# transponder-6_1_1.net
KiCad netlist of a schematic drawn in EAGLE
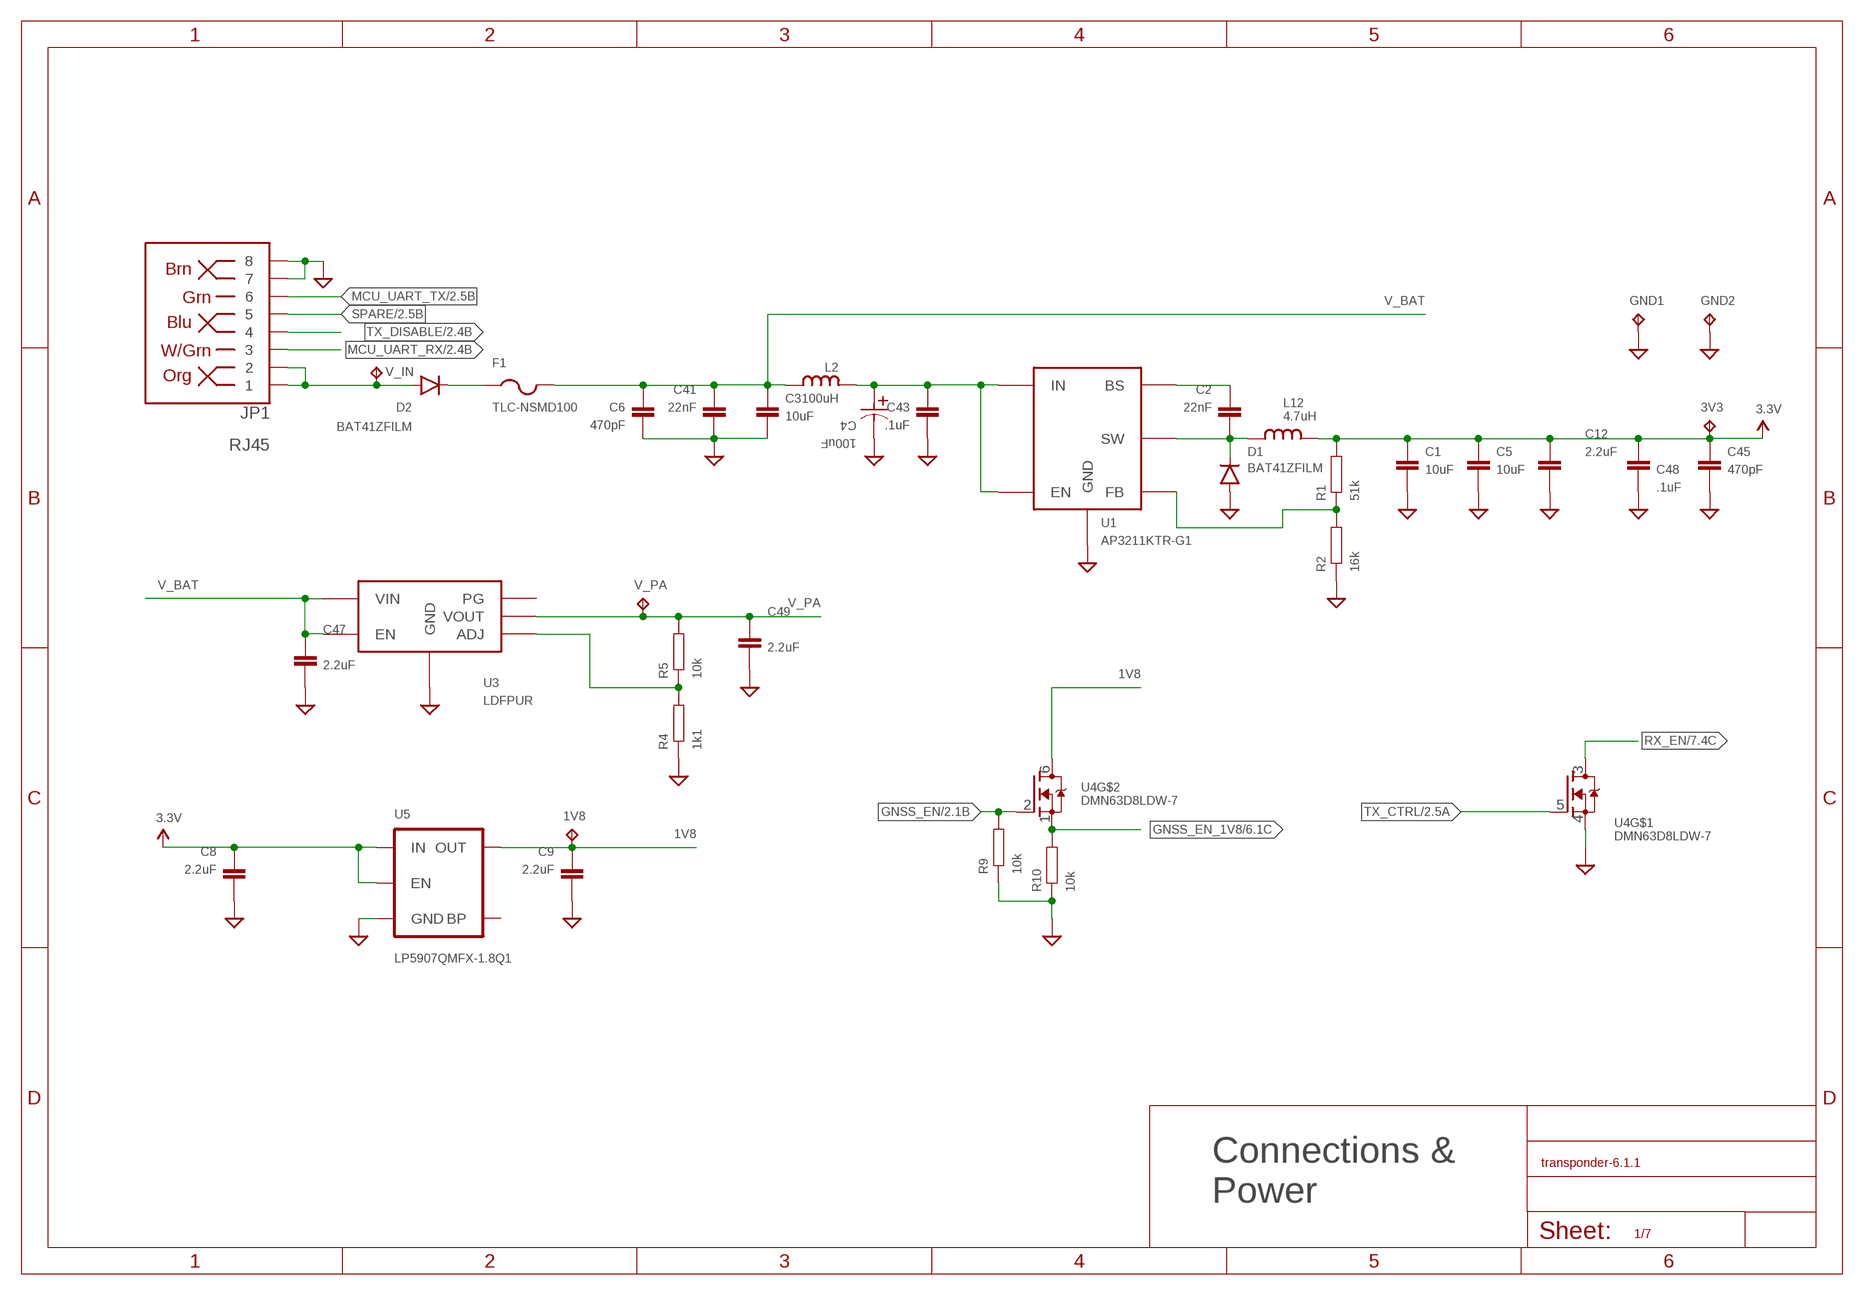
[diagram p0: schematic, sheet 1]
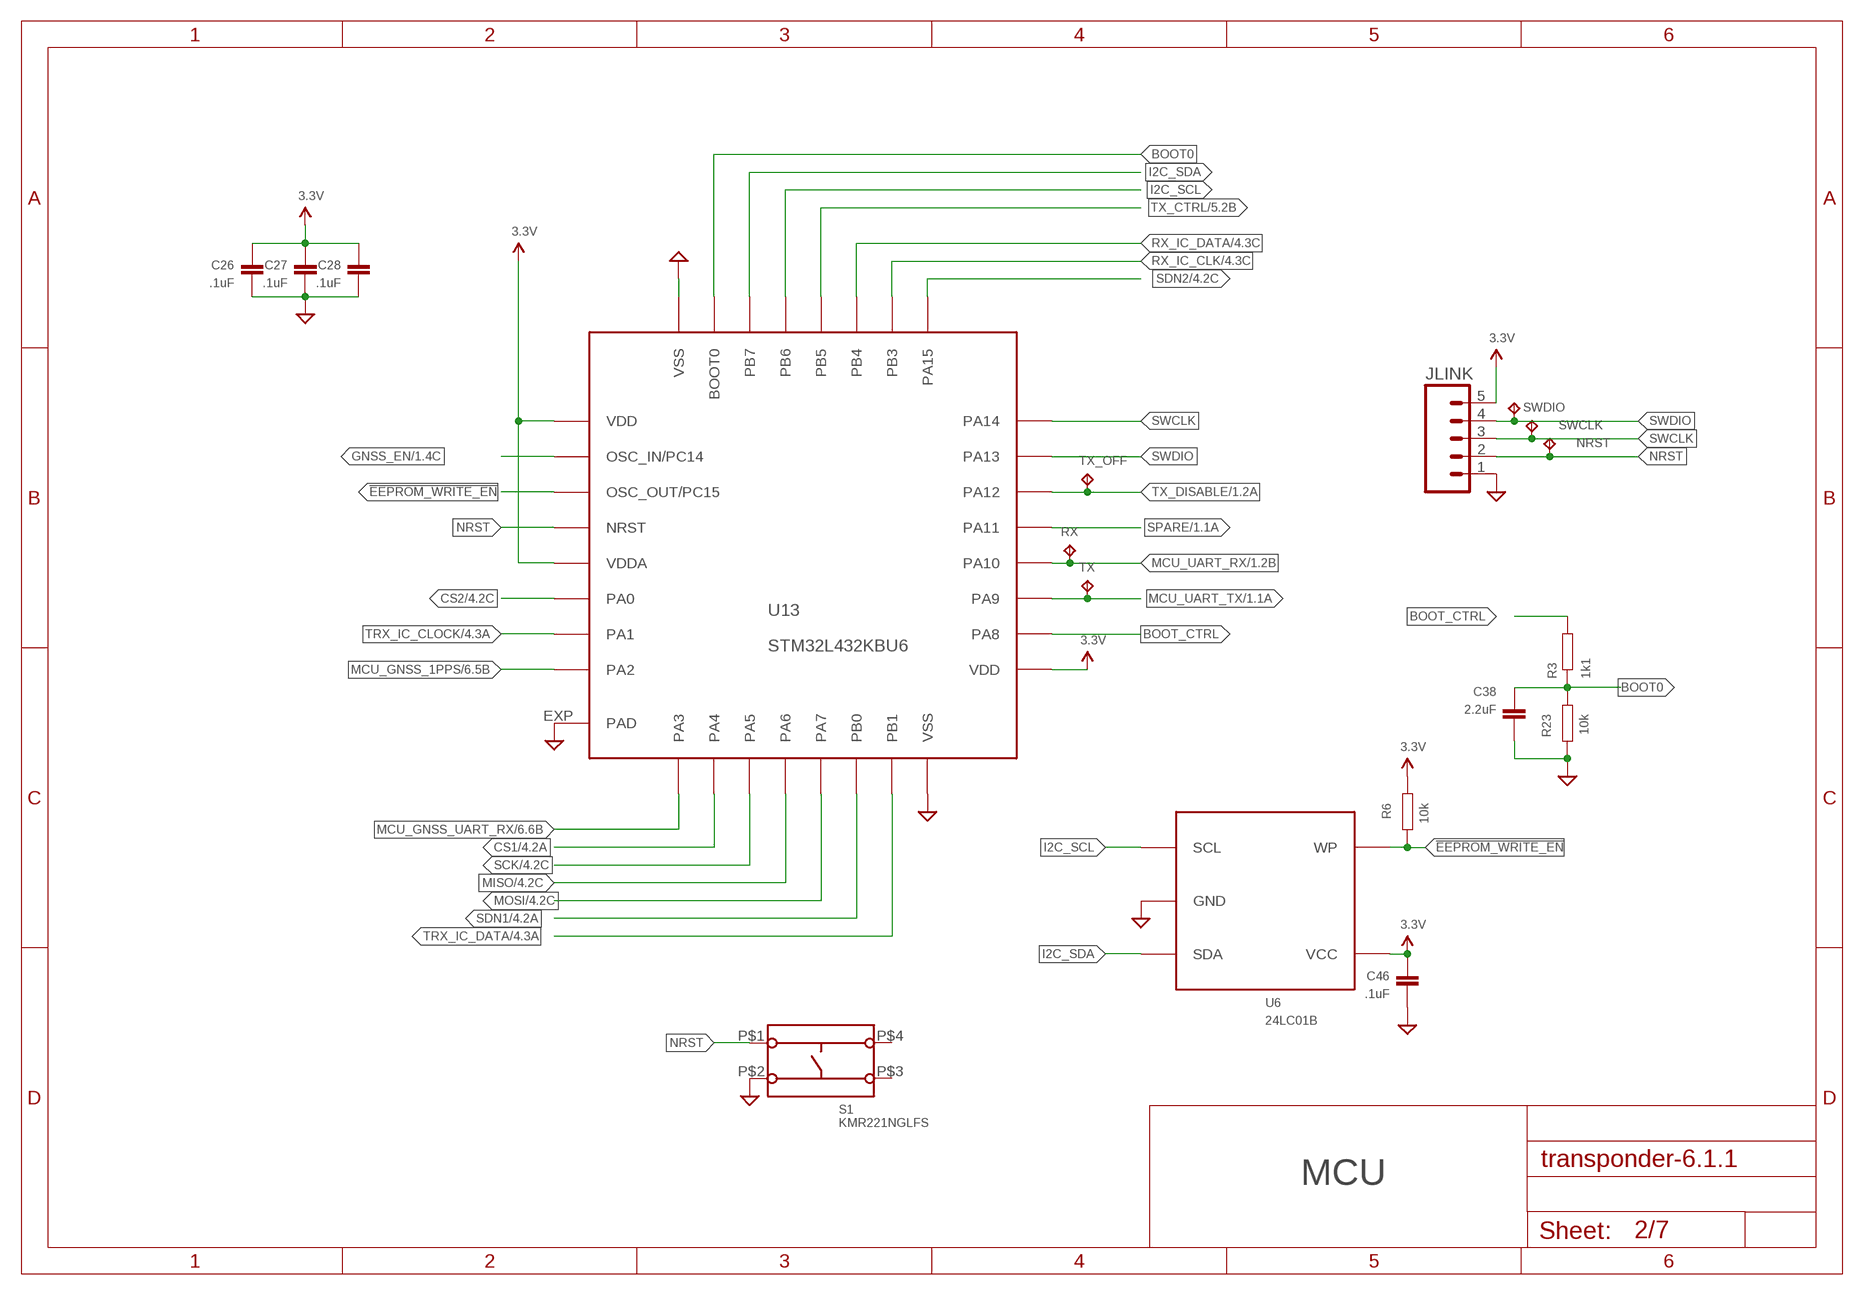
[diagram p1: schematic, sheet 2]
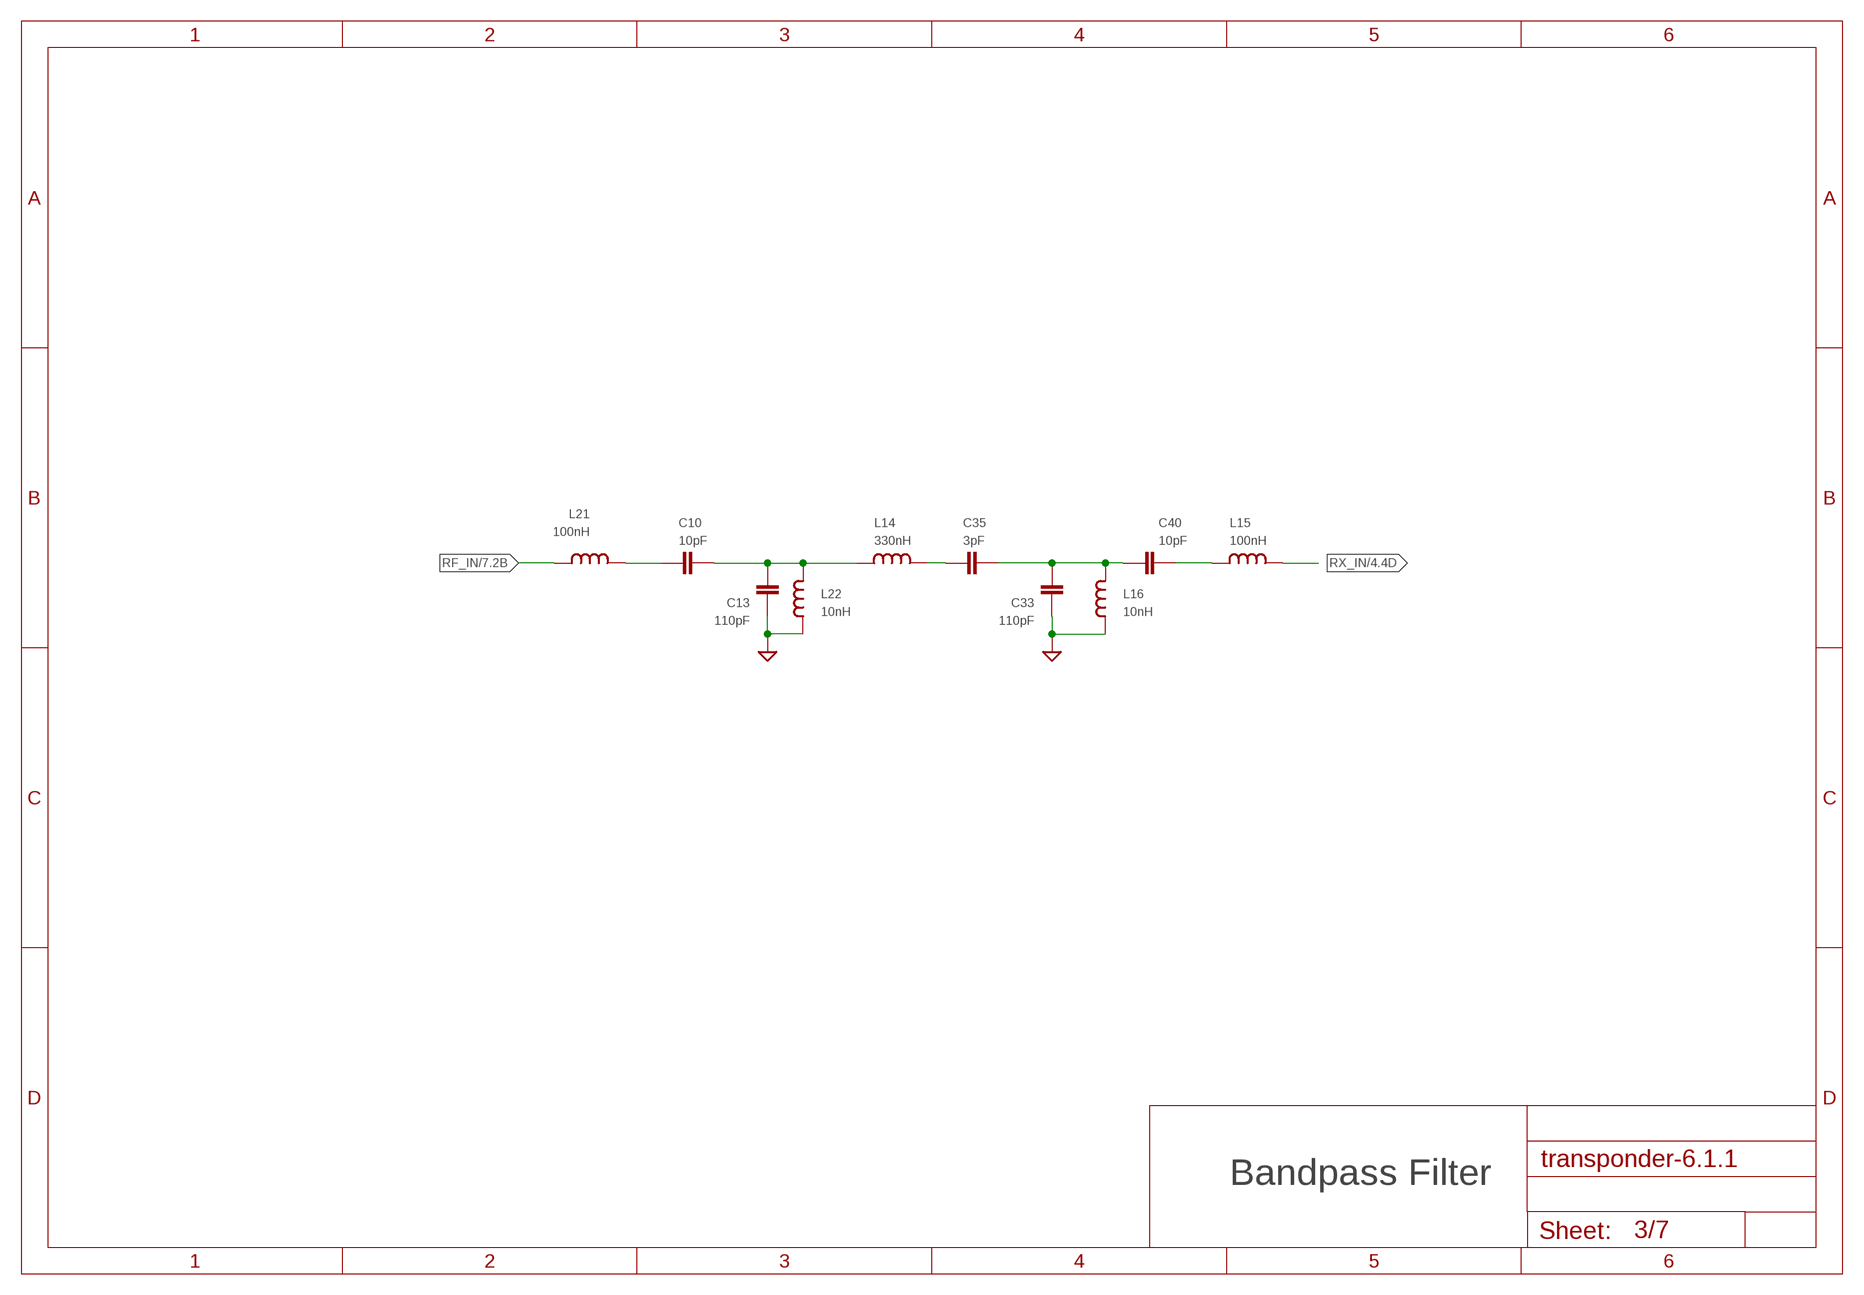
[diagram p2: schematic, sheet 3]
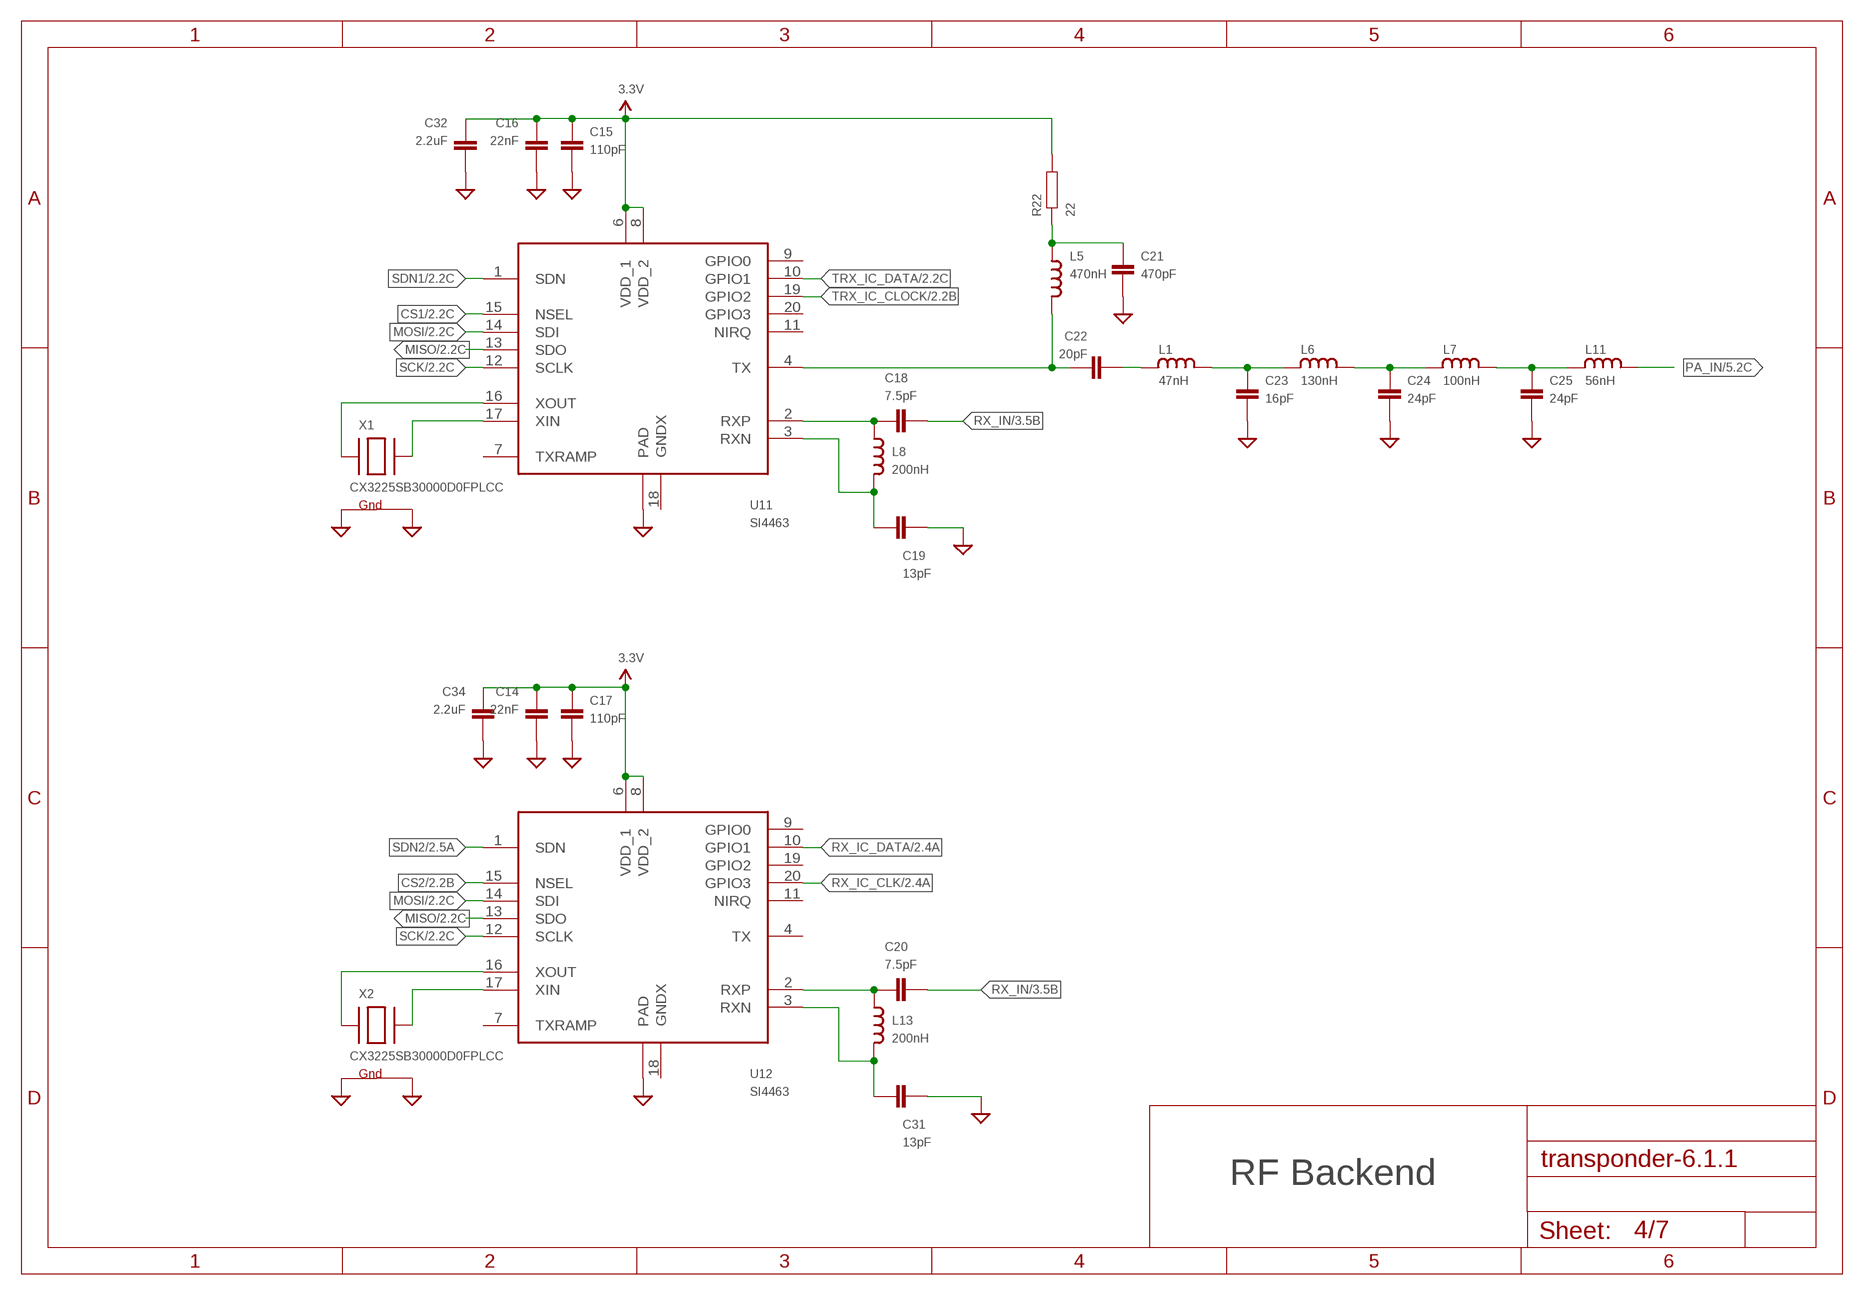
[diagram p3: schematic, sheet 4]
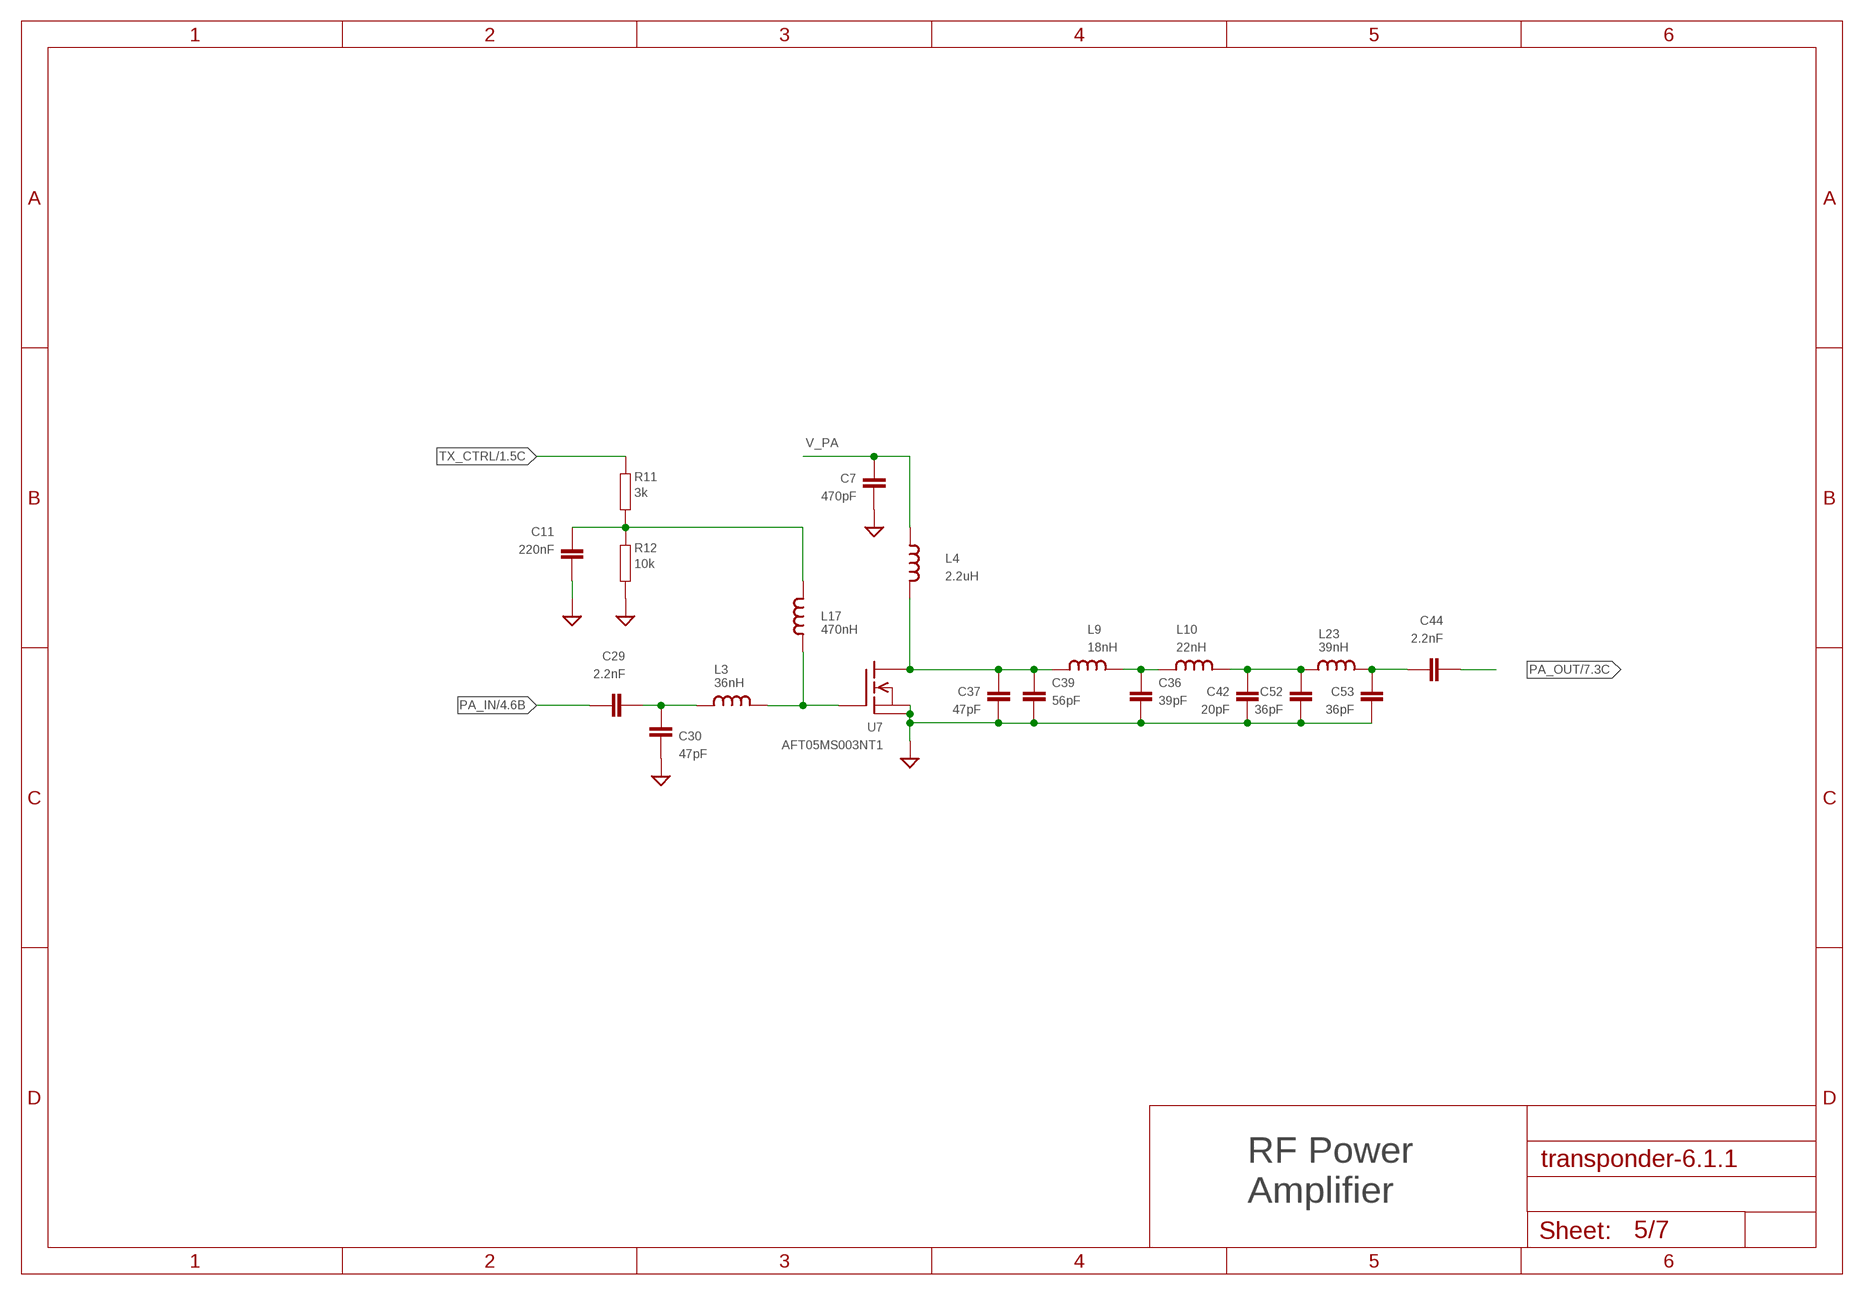
[diagram p4: schematic, sheet 5]
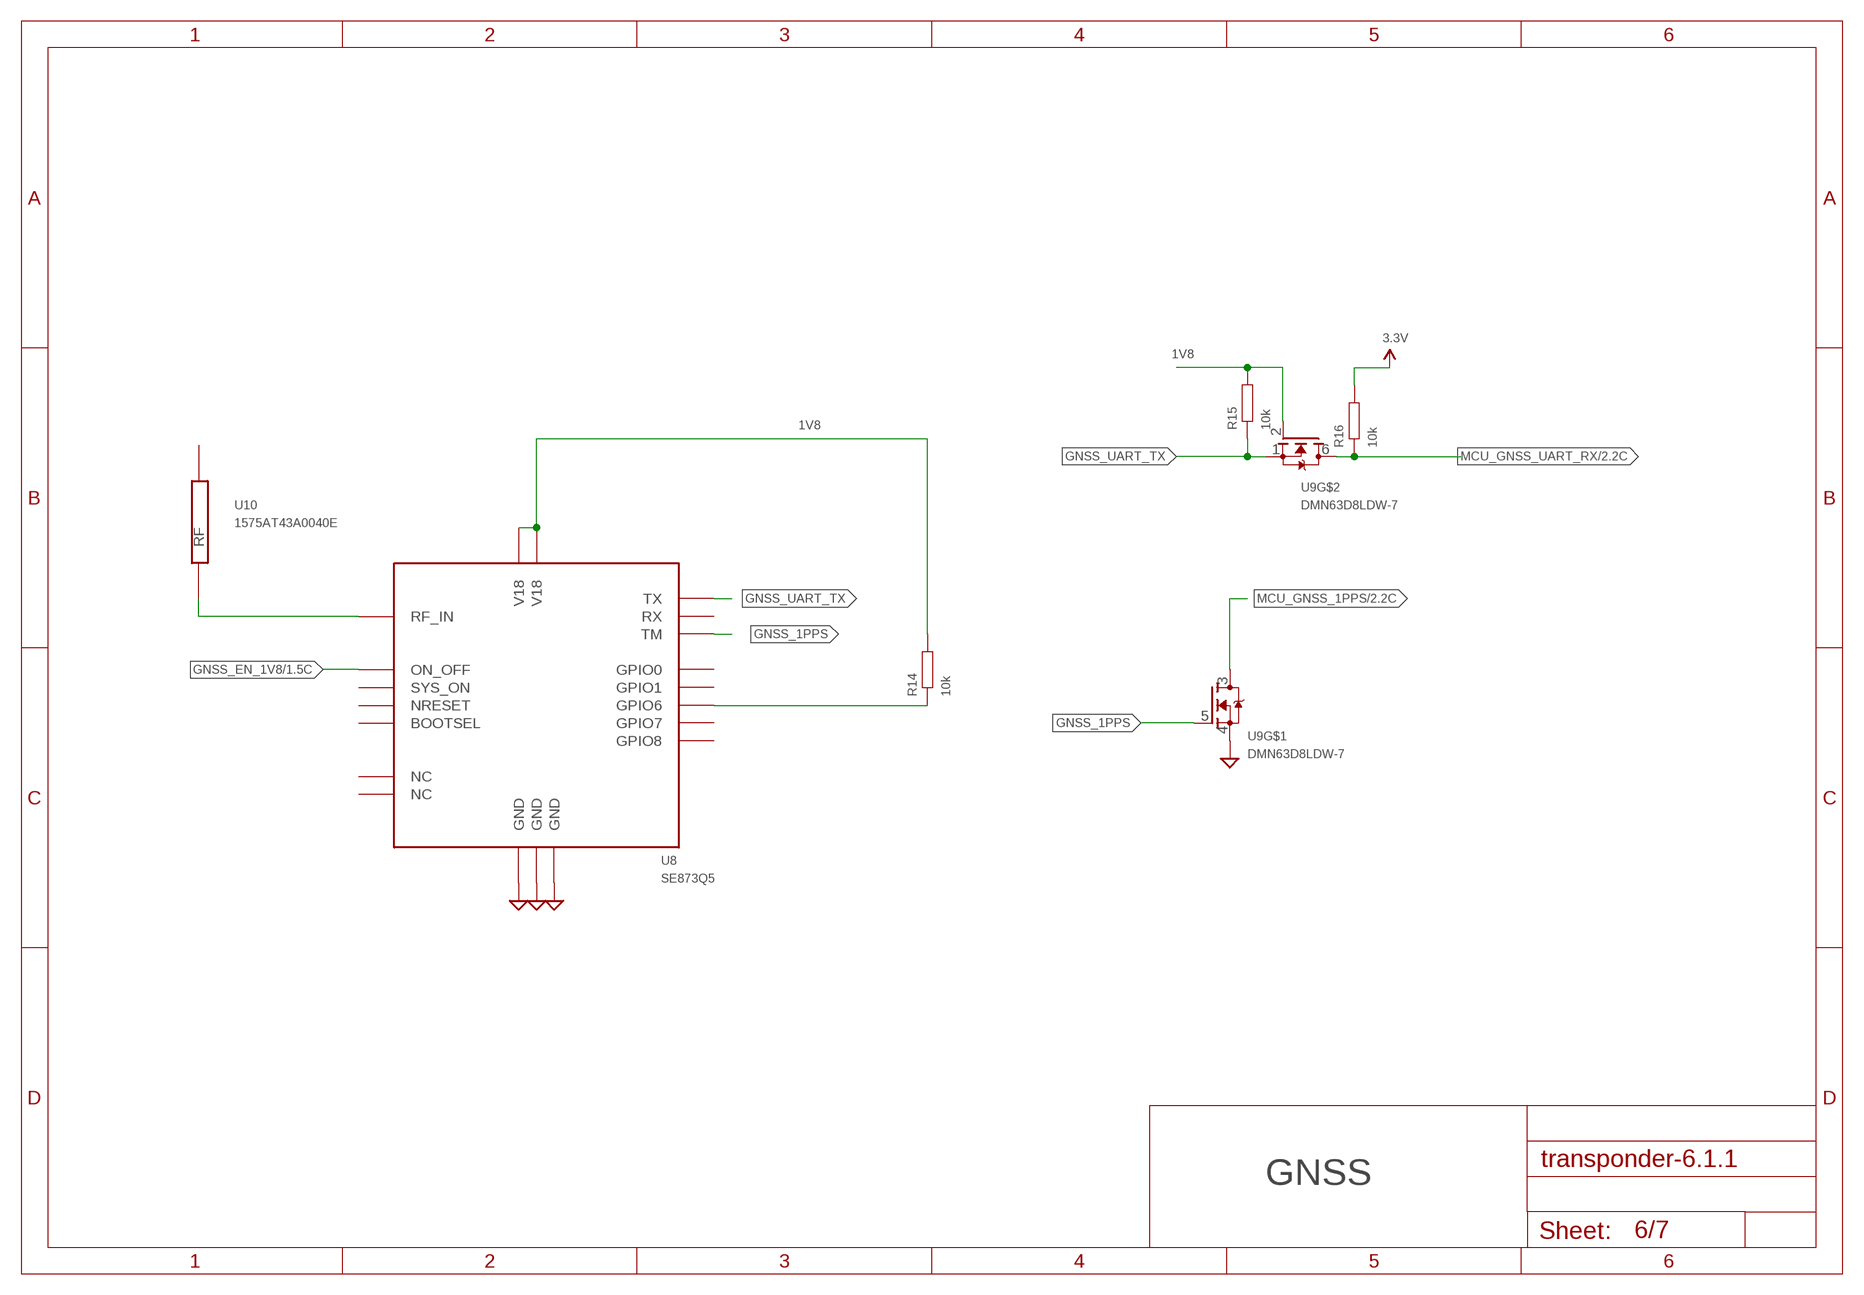
[diagram p5: schematic, sheet 6]
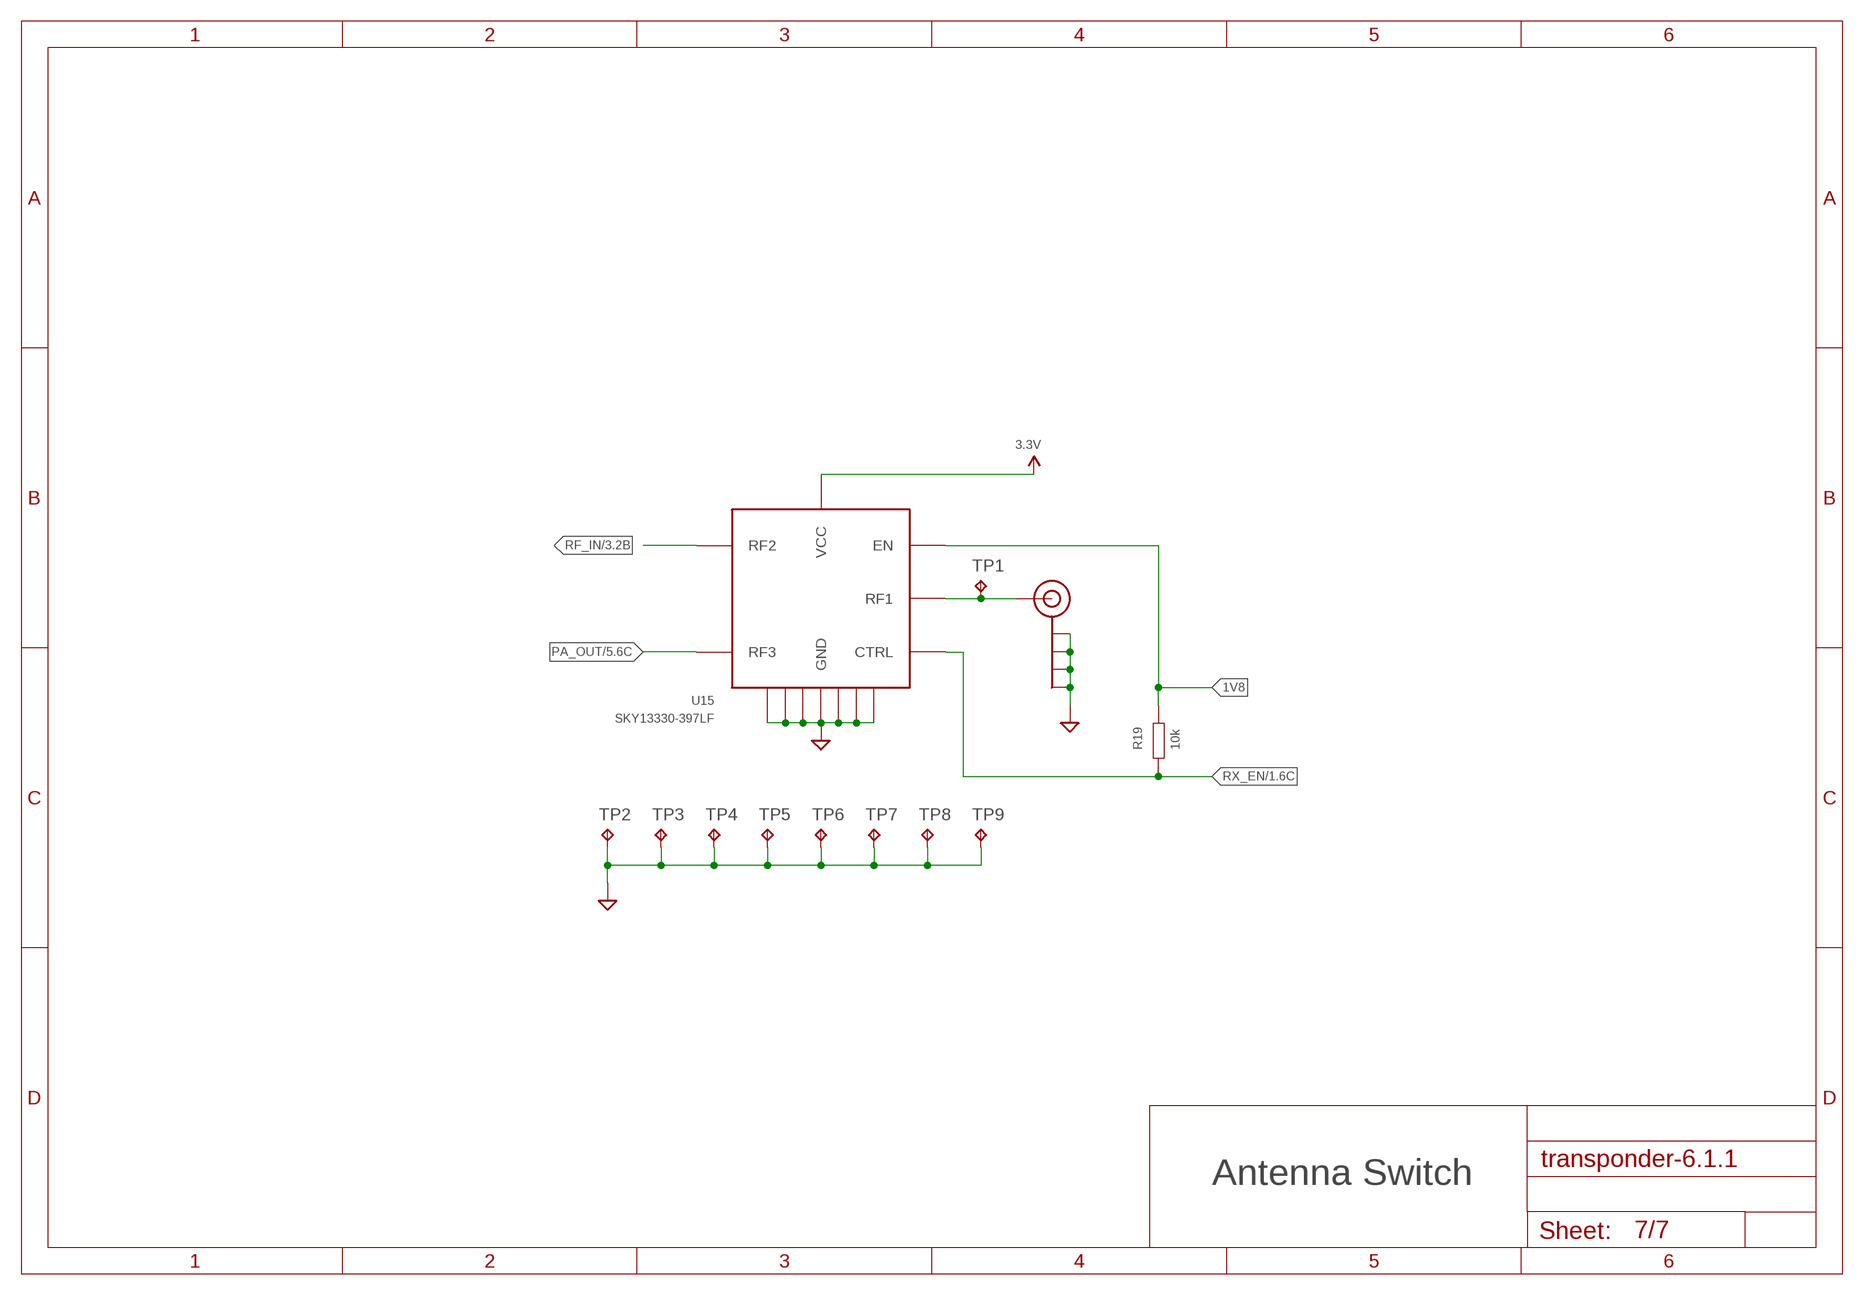
[diagram p6: schematic, sheet 7]

(export (version "E")
  (design (tool "Eeschema 10.0.6"))
  (components
    (comp (ref "C10")
      (value "10pF")
      (footprint "eagle-import:0603")
      (fields (field (name "PARTNO") "06035A100FAT2A"))
      (libsource (lib "eagle-import") (part "CAPACITOR0603"))
    )
    (comp (ref "C13")
      (value "110pF")
      (footprint "eagle-import:0603")
      (fields (field (name "PARTNO") "06035U111FAT2A"))
      (libsource (lib "eagle-import") (part "CAPACITOR0603"))
    )
    (comp (ref "C33")
      (value "110pF")
      (footprint "eagle-import:0603")
      (fields (field (name "PARTNO") "06035U111FAT2A"))
      (libsource (lib "eagle-import") (part "CAPACITOR0603"))
    )
    (comp (ref "C35")
      (value "3pF")
      (footprint "eagle-import:0603")
      (fields (field (name "PARTNO") "06032U3R0BAT2A"))
      (libsource (lib "eagle-import") (part "CAPACITOR0603"))
    )
    (comp (ref "C40")
      (value "10pF")
      (footprint "eagle-import:0603")
      (fields (field (name "PARTNO") "06035A100FAT2A"))
      (libsource (lib "eagle-import") (part "CAPACITOR0603"))
    )
    (comp (ref "L14")
      (value "330nH")
      (footprint "eagle-import:0603")
      (fields (field (name "PARTNO") "LQW18ANR33G00D"))
      (libsource (lib "eagle-import") (part "INDUCTOR0603"))
    )
    (comp (ref "L15")
      (value "100nH")
      (footprint "eagle-import:0603")
      (fields (field (name "PARTNO") "LQW18ANR10G00D"))
      (libsource (lib "eagle-import") (part "INDUCTOR0603"))
    )
    (comp (ref "L16")
      (value "10nH")
      (footprint "eagle-import:0603")
      (fields (field (name "PARTNO") "LQW18AN10NG00D"))
      (libsource (lib "eagle-import") (part "INDUCTOR0603"))
    )
    (comp (ref "L21")
      (value "100nH")
      (footprint "eagle-import:0603")
      (fields (field (name "PARTNO") "LQW18ANR10G00D"))
      (libsource (lib "eagle-import") (part "INDUCTOR0603"))
    )
    (comp (ref "L22")
      (value "10nH")
      (footprint "eagle-import:0603")
      (fields (field (name "PARTNO") "LQW18AN10NG00D"))
      (libsource (lib "eagle-import") (part "INDUCTOR0603"))
    )
    (comp (ref "R14")
      (value "10k")
      (footprint "eagle-import:0603-RES")
      (fields (field (name "PARTNO") "RC0603JR-0710KL"))
      (libsource (lib "eagle-import") (part "RESISTOR0603-RES"))
    )
    (comp (ref "R15")
      (value "10k")
      (footprint "eagle-import:0603-RES")
      (fields (field (name "PARTNO") "RC0603JR-0710KL"))
      (libsource (lib "eagle-import") (part "RESISTOR0603-RES"))
    )
    (comp (ref "R16")
      (value "10k")
      (footprint "eagle-import:0603-RES")
      (fields (field (name "PARTNO") "RC0603JR-0710KL"))
      (libsource (lib "eagle-import") (part "RESISTOR0603-RES"))
    )
    (comp (ref "U8")
      (value "SE873Q5")
      (footprint "eagle-import:SE873")
      (libsource (lib "eagle-import") (part "SE873"))
    )
    (comp (ref "U9")
      (value "DMN63D8LDW-7")
      (footprint "eagle-import:SOT363")
      (fields (field (name "PARTNO") "DMN63D8LDW-7"))
      (libsource (lib "eagle-import") (part "DMN63D8LDW"))
    )
    (comp (ref "U10")
      (value "1575AT43A0040E")
      (footprint "eagle-import:1575AT43A0040E")
      (libsource (lib "eagle-import") (part "1575AT43A0040E"))
    )
    (comp (ref "1V8")
      (value "TPTP16R")
      (footprint "eagle-import:TP16R")
      (libsource (lib "eagle-import") (part "TPTP16R"))
    )
    (comp (ref "3V3")
      (value "TPTP16R")
      (footprint "eagle-import:TP16R")
      (libsource (lib "eagle-import") (part "TPTP16R"))
    )
    (comp (ref "C1")
      (value "10uF")
      (footprint "eagle-import:0805")
      (fields (field (name "PARTNO") " EMK212ABJ106KG-T"))
      (libsource (lib "eagle-import") (part "CAPACITOR0805"))
    )
    (comp (ref "C2")
      (value "22nF")
      (footprint "eagle-import:0603")
      (fields (field (name "PARTNO") "GRM188R71E223KA01D"))
      (libsource (lib "eagle-import") (part "CAPACITOR0603"))
    )
    (comp (ref "C3")
      (value "10uF")
      (footprint "eagle-import:0805")
      (fields (field (name "PARTNO") " EMK212ABJ106KG-T"))
      (libsource (lib "eagle-import") (part "CAPACITOR0805"))
    )
    (comp (ref "C4")
      (value "100uF")
      (footprint "eagle-import:PCAP_6.3X5.4-ELECT")
      (fields (field (name "MF") "Nichicon") (field (name "MP") "UWX1C101MCL1GB"))
      (libsource (lib "eagle-import") (part "UWX1C101MCL1GB"))
    )
    (comp (ref "C5")
      (value "10uF")
      (footprint "eagle-import:0805")
      (fields (field (name "PARTNO") " EMK212ABJ106KG-T"))
      (libsource (lib "eagle-import") (part "CAPACITOR0805"))
    )
    (comp (ref "C6")
      (value "470pF")
      (footprint "eagle-import:0603")
      (fields (field (name "PARTNO") "GCM1885C2A471JA16J"))
      (libsource (lib "eagle-import") (part "CAPACITOR0603"))
    )
    (comp (ref "C8")
      (value "2.2uF")
      (footprint "eagle-import:0603")
      (fields (field (name "PARTNO") "EMK107BJ225KA-T"))
      (libsource (lib "eagle-import") (part "CAPACITOR0603"))
    )
    (comp (ref "C9")
      (value "2.2uF")
      (footprint "eagle-import:0603")
      (fields (field (name "PARTNO") "EMK107BJ225KA-T"))
      (libsource (lib "eagle-import") (part "CAPACITOR0603"))
    )
    (comp (ref "C12")
      (value "2.2uF")
      (footprint "eagle-import:0603")
      (fields (field (name "PARTNO") "EMK107BJ225KA-T"))
      (libsource (lib "eagle-import") (part "CAPACITOR0603"))
    )
    (comp (ref "C41")
      (value "22nF")
      (footprint "eagle-import:0603")
      (fields (field (name "PARTNO") "GRM188R71E223KA01D"))
      (libsource (lib "eagle-import") (part "CAPACITOR0603"))
    )
    (comp (ref "C43")
      (value ".1uF")
      (footprint "eagle-import:0603")
      (fields (field (name "PARTNO") "EMK107B7104KAHT"))
      (libsource (lib "eagle-import") (part "CAPACITOR0603"))
    )
    (comp (ref "C45")
      (value "470pF")
      (footprint "eagle-import:0603")
      (fields (field (name "PARTNO") "GCM1885C2A471JA16J"))
      (libsource (lib "eagle-import") (part "CAPACITOR0603"))
    )
    (comp (ref "C47")
      (value "2.2uF")
      (footprint "eagle-import:0603")
      (fields (field (name "PARTNO") "EMK107BJ225KA-T"))
      (libsource (lib "eagle-import") (part "CAPACITOR0603"))
    )
    (comp (ref "C48")
      (value ".1uF")
      (footprint "eagle-import:0603")
      (fields (field (name "PARTNO") "EMK107B7104KAHT"))
      (libsource (lib "eagle-import") (part "CAPACITOR0603"))
    )
    (comp (ref "C49")
      (value "2.2uF")
      (footprint "eagle-import:0603")
      (fields (field (name "PARTNO") "EMK107BJ225KA-T"))
      (libsource (lib "eagle-import") (part "CAPACITOR0603"))
    )
    (comp (ref "D1")
      (value "BAT41ZFILM")
      (footprint "eagle-import:SOD-123")
      (libsource (lib "eagle-import") (part "DIODESOD123"))
    )
    (comp (ref "D2")
      (value "BAT41ZFILM")
      (footprint "eagle-import:SOD-123")
      (libsource (lib "eagle-import") (part "DIODESOD123"))
    )
    (comp (ref "F1")
      (value "TLC-NSMD100")
      (footprint "eagle-import:R1206")
      (libsource (lib "eagle-import") (part "PTCFUSE-1206"))
    )
    (comp (ref "GND1")
      (value "TPTP16R")
      (footprint "eagle-import:TP16R")
      (libsource (lib "eagle-import") (part "TPTP16R"))
    )
    (comp (ref "GND2")
      (value "TPTP16R")
      (footprint "eagle-import:TP16R")
      (libsource (lib "eagle-import") (part "TPTP16R"))
    )
    (comp (ref "JP1")
      (value "RJ45")
      (footprint "eagle-import:RJ45-8")
      (fields (field (name "PARTNO") "54602-908LF"))
      (libsource (lib "eagle-import") (part "RJ45-8PTH"))
    )
    (comp (ref "L2")
      (value "100uH")
      (footprint "eagle-import:1206")
      (fields (field (name "PARTNO") "CBC3225T101KRV"))
      (libsource (lib "eagle-import") (part "INDUCTOR1206"))
    )
    (comp (ref "L12")
      (value "4.7uH")
      (footprint "eagle-import:0805")
      (fields (field (name "PARTNO") "MLZ2012M4R7WT000"))
      (libsource (lib "eagle-import") (part "INDUCTOR0805"))
    )
    (comp (ref "R1")
      (value "51k")
      (footprint "eagle-import:0603-RES")
      (fields (field (name "PARTNO") "RC0603JR-0751KL"))
      (libsource (lib "eagle-import") (part "RESISTOR0603-RES"))
    )
    (comp (ref "R2")
      (value "16k")
      (footprint "eagle-import:0603-RES")
      (fields (field (name "PARTNO") "RC0603FR-1016KL"))
      (libsource (lib "eagle-import") (part "RESISTOR0603-RES"))
    )
    (comp (ref "R4")
      (value "1k1")
      (footprint "eagle-import:0603-RES")
      (fields (field (name "PARTNO") "RC0603JR-071K1L"))
      (libsource (lib "eagle-import") (part "RESISTOR0603-RES"))
    )
    (comp (ref "R5")
      (value "10k")
      (footprint "eagle-import:0603-RES")
      (fields (field (name "PARTNO") "RC0603JR-0710KL"))
      (libsource (lib "eagle-import") (part "RESISTOR0603-RES"))
    )
    (comp (ref "R9")
      (value "10k")
      (footprint "eagle-import:0603-RES")
      (fields (field (name "PARTNO") "RC0603JR-0710KL"))
      (libsource (lib "eagle-import") (part "RESISTOR0603-RES"))
    )
    (comp (ref "R10")
      (value "10k")
      (footprint "eagle-import:0603-RES")
      (fields (field (name "PARTNO") "RC0603JR-0710KL"))
      (libsource (lib "eagle-import") (part "RESISTOR0603-RES"))
    )
    (comp (ref "U1")
      (value "AP3211KTR-G1")
      (footprint "eagle-import:SOT23-6")
      (libsource (lib "eagle-import") (part "AP3211"))
    )
    (comp (ref "U3")
      (value "LDFPUR")
      (footprint "eagle-import:DFN-6")
      (libsource (lib "eagle-import") (part "LDF"))
    )
    (comp (ref "U4")
      (value "DMN63D8LDW-7")
      (footprint "eagle-import:SOT363")
      (fields (field (name "PARTNO") "DMN63D8LDW-7"))
      (libsource (lib "eagle-import") (part "DMN63D8LDW"))
    )
    (comp (ref "U5")
      (value "LP5907QMFX-1.8Q1")
      (footprint "eagle-import:SOT23-5")
      (fields (field (name "PARTNO") "LP5907QMFX-1.8Q1 "))
      (libsource (lib "eagle-import") (part "V_REG_LDOSMD"))
    )
    (comp (ref "V_IN")
      (value "TPTP16R")
      (footprint "eagle-import:TP16R")
      (libsource (lib "eagle-import") (part "TPTP16R"))
    )
    (comp (ref "V_PA")
      (value "TPTP16R")
      (footprint "eagle-import:TP16R")
      (libsource (lib "eagle-import") (part "TPTP16R"))
    )
    (comp (ref "J$1")
      (value "SMA_EDGE")
      (footprint "eagle-import:SMA-EDGE")
      (libsource (lib "eagle-import") (part "SMA_EDGE"))
    )
    (comp (ref "R19")
      (value "10k")
      (footprint "eagle-import:0603-RES")
      (fields (field (name "PARTNO") "RC0603JR-0710KL"))
      (libsource (lib "eagle-import") (part "RESISTOR0603-RES"))
    )
    (comp (ref "TP1")
      (value "TPTP10R")
      (footprint "eagle-import:TP10R")
      (libsource (lib "eagle-import") (part "TPTP10R"))
    )
    (comp (ref "TP2")
      (value "TPTP10R")
      (footprint "eagle-import:TP10R")
      (libsource (lib "eagle-import") (part "TPTP10R"))
    )
    (comp (ref "TP3")
      (value "TPTP10R")
      (footprint "eagle-import:TP10R")
      (libsource (lib "eagle-import") (part "TPTP10R"))
    )
    (comp (ref "TP4")
      (value "TPTP10R")
      (footprint "eagle-import:TP10R")
      (libsource (lib "eagle-import") (part "TPTP10R"))
    )
    (comp (ref "TP5")
      (value "TPTP10R")
      (footprint "eagle-import:TP10R")
      (libsource (lib "eagle-import") (part "TPTP10R"))
    )
    (comp (ref "TP6")
      (value "TPTP10R")
      (footprint "eagle-import:TP10R")
      (libsource (lib "eagle-import") (part "TPTP10R"))
    )
    (comp (ref "TP7")
      (value "TPTP10R")
      (footprint "eagle-import:TP10R")
      (libsource (lib "eagle-import") (part "TPTP10R"))
    )
    (comp (ref "TP8")
      (value "TPTP10R")
      (footprint "eagle-import:TP10R")
      (libsource (lib "eagle-import") (part "TPTP10R"))
    )
    (comp (ref "TP9")
      (value "TPTP10R")
      (footprint "eagle-import:TP10R")
      (libsource (lib "eagle-import") (part "TPTP10R"))
    )
    (comp (ref "U15")
      (value "SKY13330-397LF")
      (footprint "eagle-import:QFN12")
      (libsource (lib "eagle-import") (part "SKYWORKS-13330397LF"))
    )
    (comp (ref "C26")
      (value ".1uF")
      (footprint "eagle-import:0603")
      (fields (field (name "PARTNO") "EMK107B7104KAHT"))
      (libsource (lib "eagle-import") (part "CAPACITOR0603"))
    )
    (comp (ref "C27")
      (value ".1uF")
      (footprint "eagle-import:0603")
      (fields (field (name "PARTNO") "EMK107B7104KAHT"))
      (libsource (lib "eagle-import") (part "CAPACITOR0603"))
    )
    (comp (ref "C28")
      (value ".1uF")
      (footprint "eagle-import:0603")
      (fields (field (name "PARTNO") "EMK107B7104KAHT"))
      (libsource (lib "eagle-import") (part "CAPACITOR0603"))
    )
    (comp (ref "C38")
      (value "2.2uF")
      (footprint "eagle-import:0603")
      (fields (field (name "PARTNO") "EMK107BJ225KA-T"))
      (libsource (lib "eagle-import") (part "CAPACITOR0603"))
    )
    (comp (ref "C46")
      (value ".1uF")
      (footprint "eagle-import:0603")
      (fields (field (name "PARTNO") "EMK107B7104KAHT"))
      (libsource (lib "eagle-import") (part "CAPACITOR0603"))
    )
    (comp (ref "JLINK")
      (value "M05PTH")
      (footprint "eagle-import:1X05")
      (libsource (lib "eagle-import") (part "M05PTH"))
    )
    (comp (ref "NRST")
      (value "TPTP16R")
      (footprint "eagle-import:TP16R")
      (libsource (lib "eagle-import") (part "TPTP16R"))
    )
    (comp (ref "R3")
      (value "1k1")
      (footprint "eagle-import:0603-RES")
      (fields (field (name "PARTNO") "RC0603JR-071K1L"))
      (libsource (lib "eagle-import") (part "RESISTOR0603-RES"))
    )
    (comp (ref "R6")
      (value "10k")
      (footprint "eagle-import:0603-RES")
      (fields (field (name "PARTNO") "RC0603JR-0710KL"))
      (libsource (lib "eagle-import") (part "RESISTOR0603-RES"))
    )
    (comp (ref "R23")
      (value "10k")
      (footprint "eagle-import:0603-RES")
      (fields (field (name "PARTNO") "RC0603JR-0710KL"))
      (libsource (lib "eagle-import") (part "RESISTOR0603-RES"))
    )
    (comp (ref "RX")
      (value "TPTP12R")
      (footprint "eagle-import:TP12R")
      (libsource (lib "eagle-import") (part "TPTP12R"))
    )
    (comp (ref "S1")
      (value "KMR221NGLFS")
      (footprint "eagle-import:KMR221NGLFS")
      (libsource (lib "eagle-import") (part "KMR221NGLFS"))
    )
    (comp (ref "SWCLK")
      (value "TPTP16R")
      (footprint "eagle-import:TP16R")
      (libsource (lib "eagle-import") (part "TPTP16R"))
    )
    (comp (ref "SWDIO")
      (value "TPTP16R")
      (footprint "eagle-import:TP16R")
      (libsource (lib "eagle-import") (part "TPTP16R"))
    )
    (comp (ref "TX")
      (value "TPTP12R")
      (footprint "eagle-import:TP12R")
      (libsource (lib "eagle-import") (part "TPTP12R"))
    )
    (comp (ref "TX_OFF")
      (value "TPTP16R")
      (footprint "eagle-import:TP16R")
      (libsource (lib "eagle-import") (part "TPTP16R"))
    )
    (comp (ref "U6")
      (value "24LC01B")
      (footprint "eagle-import:SOT23-5")
      (fields (field (name "PARTNO") "24LC01BT-I/OT"))
      (libsource (lib "eagle-import") (part "24LC01B"))
    )
    (comp (ref "U13")
      (value "STM32L432KBU6")
      (footprint "eagle-import:QFN32")
      (libsource (lib "eagle-import") (part "STM32L432KXXX"))
    )
    (comp (ref "C14")
      (value "22nF")
      (footprint "eagle-import:0603")
      (fields (field (name "PARTNO") "GRM188R71E223KA01D"))
      (libsource (lib "eagle-import") (part "CAPACITOR0603"))
    )
    (comp (ref "C15")
      (value "110pF")
      (footprint "eagle-import:0603")
      (fields (field (name "PARTNO") "06035U111FAT2A"))
      (libsource (lib "eagle-import") (part "CAPACITOR0603"))
    )
    (comp (ref "C16")
      (value "22nF")
      (footprint "eagle-import:0603")
      (fields (field (name "PARTNO") "GRM188R71E223KA01D"))
      (libsource (lib "eagle-import") (part "CAPACITOR0603"))
    )
    (comp (ref "C17")
      (value "110pF")
      (footprint "eagle-import:0603")
      (fields (field (name "PARTNO") "06035U111FAT2A"))
      (libsource (lib "eagle-import") (part "CAPACITOR0603"))
    )
    (comp (ref "C18")
      (value "7.5pF")
      (footprint "eagle-import:0603")
      (fields (field (name "PARTNO") "GRM1885C1H7R5DA01D"))
      (libsource (lib "eagle-import") (part "CAPACITOR0603"))
    )
    (comp (ref "C19")
      (value "13pF")
      (footprint "eagle-import:0603")
      (fields (field (name "PARTNO") "GRM1885C1H130JA01D"))
      (libsource (lib "eagle-import") (part "CAPACITOR0603"))
    )
    (comp (ref "C20")
      (value "7.5pF")
      (footprint "eagle-import:0603")
      (fields (field (name "PARTNO") "GRM1885C1H7R5DA01D"))
      (libsource (lib "eagle-import") (part "CAPACITOR0603"))
    )
    (comp (ref "C21")
      (value "470pF")
      (footprint "eagle-import:0603")
      (fields (field (name "PARTNO") "GCM1885C2A471JA16J"))
      (libsource (lib "eagle-import") (part "CAPACITOR0603"))
    )
    (comp (ref "C22")
      (value "20pF")
      (footprint "eagle-import:0603")
      (fields (field (name "PARTNO") "GRM1885C1H200JA01D"))
      (libsource (lib "eagle-import") (part "CAPACITOR0603"))
    )
    (comp (ref "C23")
      (value "16pF")
      (footprint "eagle-import:0603")
      (fields (field (name "PARTNO") "GCM1885C2A160JA16D"))
      (libsource (lib "eagle-import") (part "CAPACITOR0603"))
    )
    (comp (ref "C24")
      (value "24pF")
      (footprint "eagle-import:0603")
      (fields (field (name "PARTNO") "GCM1885C2A240JA16D"))
      (libsource (lib "eagle-import") (part "CAPACITOR0603"))
    )
    (comp (ref "C25")
      (value "24pF")
      (footprint "eagle-import:0603")
      (fields (field (name "PARTNO") "GCM1885C2A240JA16D"))
      (libsource (lib "eagle-import") (part "CAPACITOR0603"))
    )
    (comp (ref "C31")
      (value "13pF")
      (footprint "eagle-import:0603")
      (fields (field (name "PARTNO") "GRM1885C1H130JA01D"))
      (libsource (lib "eagle-import") (part "CAPACITOR0603"))
    )
    (comp (ref "C32")
      (value "2.2uF")
      (footprint "eagle-import:0603")
      (fields (field (name "PARTNO") "EMK107BJ225KA-T"))
      (libsource (lib "eagle-import") (part "CAPACITOR0603"))
    )
    (comp (ref "C34")
      (value "2.2uF")
      (footprint "eagle-import:0603")
      (fields (field (name "PARTNO") "EMK107BJ225KA-T"))
      (libsource (lib "eagle-import") (part "CAPACITOR0603"))
    )
    (comp (ref "L1")
      (value "47nH")
      (footprint "eagle-import:0603")
      (fields (field (name "PARTNO") "LQW18AS47NG00D"))
      (libsource (lib "eagle-import") (part "INDUCTOR0603"))
    )
    (comp (ref "L5")
      (value "470nH")
      (footprint "eagle-import:0603")
      (fields (field (name "PARTNO") "HK1608R47J-T"))
      (libsource (lib "eagle-import") (part "INDUCTOR0603"))
    )
    (comp (ref "L6")
      (value "130nH")
      (footprint "eagle-import:0603")
      (fields (field (name "PARTNO") "LQW18ANR13G00D"))
      (libsource (lib "eagle-import") (part "INDUCTOR0603"))
    )
    (comp (ref "L7")
      (value "100nH")
      (footprint "eagle-import:0603")
      (fields (field (name "PARTNO") "LQW18ANR10G00D"))
      (libsource (lib "eagle-import") (part "INDUCTOR0603"))
    )
    (comp (ref "L8")
      (value "200nH")
      (footprint "eagle-import:0603")
      (fields (field (name "PARTNO") "LQW18ANR20J00D"))
      (libsource (lib "eagle-import") (part "INDUCTOR0603"))
    )
    (comp (ref "L11")
      (value "56nH")
      (footprint "eagle-import:0603")
      (fields (field (name "PARTNO") "LQW18AN56NG00D"))
      (libsource (lib "eagle-import") (part "INDUCTOR0603"))
    )
    (comp (ref "L13")
      (value "200nH")
      (footprint "eagle-import:0603")
      (fields (field (name "PARTNO") "LQW18ANR20J00D"))
      (libsource (lib "eagle-import") (part "INDUCTOR0603"))
    )
    (comp (ref "R22")
      (value "22")
      (footprint "eagle-import:0603-RES")
      (fields (field (name "PARTNO") "RC0603JR-0722RL"))
      (libsource (lib "eagle-import") (part "RESISTOR0603-RES"))
    )
    (comp (ref "U11")
      (value "SI4463")
      (footprint "eagle-import:SI4463")
      (fields (field (name "PARTNO") "SI4463-C2A-GMR"))
      (libsource (lib "eagle-import") (part "SI4463"))
    )
    (comp (ref "U12")
      (value "SI4463")
      (footprint "eagle-import:SI4463")
      (fields (field (name "PARTNO") "SI4463-C2A-GMR"))
      (libsource (lib "eagle-import") (part "SI4463"))
    )
    (comp (ref "X1")
      (value "CX3225SB30000D0FPLCC")
      (footprint "eagle-import:NX3225")
      (libsource (lib "eagle-import") (part "XTAL-4-3225"))
    )
    (comp (ref "X2")
      (value "CX3225SB30000D0FPLCC")
      (footprint "eagle-import:NX3225")
      (libsource (lib "eagle-import") (part "XTAL-4-3225"))
    )
    (comp (ref "C7")
      (value "470pF")
      (footprint "eagle-import:0603")
      (fields (field (name "PARTNO") "GCM1885C2A471JA16J"))
      (libsource (lib "eagle-import") (part "CAPACITOR0603"))
    )
    (comp (ref "C11")
      (value "220nF")
      (footprint "eagle-import:0603")
      (fields (field (name "PARTNO") "GRM188R71E224JA88D"))
      (libsource (lib "eagle-import") (part "CAPACITOR0603"))
    )
    (comp (ref "C29")
      (value "2.2nF")
      (footprint "eagle-import:0603")
      (fields (field (name "PARTNO") "GRM1885C1H222JA01J"))
      (libsource (lib "eagle-import") (part "CAPACITOR0603"))
    )
    (comp (ref "C30")
      (value "47pF")
      (footprint "eagle-import:0603")
      (fields (field (name "PARTNO") "Murata Electronics"))
      (libsource (lib "eagle-import") (part "CAPACITOR0603"))
    )
    (comp (ref "C36")
      (value "39pF")
      (footprint "eagle-import:0603")
      (fields (field (name "PARTNO") "GRM1885C1H390JA01D"))
      (libsource (lib "eagle-import") (part "CAPACITOR0603"))
    )
    (comp (ref "C37")
      (value "47pF")
      (footprint "eagle-import:0603")
      (fields (field (name "PARTNO") "Murata Electronics"))
      (libsource (lib "eagle-import") (part "CAPACITOR0603"))
    )
    (comp (ref "C39")
      (value "56pF")
      (footprint "eagle-import:0603")
      (fields (field (name "PARTNO") "GRM1885C1H560JA01D"))
      (libsource (lib "eagle-import") (part "CAPACITOR0603"))
    )
    (comp (ref "C42")
      (value "20pF")
      (footprint "eagle-import:0603")
      (fields (field (name "PARTNO") "GRM1885C1H200JA01D"))
      (libsource (lib "eagle-import") (part "CAPACITOR0603"))
    )
    (comp (ref "C44")
      (value "2.2nF")
      (footprint "eagle-import:0603")
      (fields (field (name "PARTNO") "GRM1885C1H222JA01J"))
      (libsource (lib "eagle-import") (part "CAPACITOR0603"))
    )
    (comp (ref "C52")
      (value "36pF")
      (footprint "eagle-import:0603")
      (fields (field (name "PARTNO") "06035U360FAT2A"))
      (libsource (lib "eagle-import") (part "CAPACITOR0603"))
    )
    (comp (ref "C53")
      (value "36pF")
      (footprint "eagle-import:0603")
      (fields (field (name "PARTNO") "06035U360FAT2A"))
      (libsource (lib "eagle-import") (part "CAPACITOR0603"))
    )
    (comp (ref "L3")
      (value "36nH")
      (footprint "eagle-import:0603")
      (fields (field (name "PARTNO") "LQW18AS36NG00D"))
      (libsource (lib "eagle-import") (part "INDUCTOR0603"))
    )
    (comp (ref "L4")
      (value "2.2uH")
      (footprint "eagle-import:0805")
      (fields (field (name "PARTNO") "BRC2012T2R2MD"))
      (libsource (lib "eagle-import") (part "INDUCTOR0805"))
    )
    (comp (ref "L9")
      (value "18nH")
      (footprint "eagle-import:0603")
      (fields (field (name "PARTNO") "LQW18AN18NG00D"))
      (libsource (lib "eagle-import") (part "INDUCTOR0603"))
    )
    (comp (ref "L10")
      (value "22nH")
      (footprint "eagle-import:0603")
      (fields (field (name "PARTNO") "LQW18AN22NJ00D"))
      (libsource (lib "eagle-import") (part "INDUCTOR0603"))
    )
    (comp (ref "L17")
      (value "470nH")
      (footprint "eagle-import:0603")
      (fields (field (name "PARTNO") "HK1608R47J-T"))
      (libsource (lib "eagle-import") (part "INDUCTOR0603"))
    )
    (comp (ref "L23")
      (value "39nH")
      (footprint "eagle-import:0603")
      (fields (field (name "PARTNO") "LQW18AS36NG00D"))
      (libsource (lib "eagle-import") (part "INDUCTOR0603"))
    )
    (comp (ref "R11")
      (value "3k")
      (footprint "eagle-import:0603-RES")
      (fields (field (name "PARTNO") "RC0603JR-073KL"))
      (libsource (lib "eagle-import") (part "RESISTOR0603-RES"))
    )
    (comp (ref "R12")
      (value "10k")
      (footprint "eagle-import:0603-RES")
      (fields (field (name "PARTNO") "RC0603JR-0710KL"))
      (libsource (lib "eagle-import") (part "RESISTOR0603-RES"))
    )
    (comp (ref "U7")
      (value "AFT05MS003NT1")
      (footprint "eagle-import:SOT-89")
      (libsource (lib "eagle-import") (part "AFT0SMS003N"))
    )
  )
  (nets
    (net (code "1") (name "1V8") (class "Default")
      (node (ref "1V8") (pin "TP") (pinfunction "TP_TP") (pintype "input"))
      (node (ref "C9") (pin "P$1") (pinfunction "1_P$1") (pintype "passive"))
      (node (ref "R14") (pin "2") (pinfunction "2_2") (pintype "passive"))
      (node (ref "R15") (pin "2") (pinfunction "2_2") (pintype "passive"))
      (node (ref "R19") (pin "2") (pinfunction "2_2") (pintype "passive"))
      (node (ref "U15") (pin "P$8") (pinfunction "EN_P$8") (pintype "bidirectional"))
      (node (ref "U4") (pin "6") (pinfunction "D_6") (pintype "bidirectional"))
      (node (ref "U5") (pin "5") (pinfunction "OUT_5") (pintype "passive"))
      (node (ref "U8") (pin "P$19") (pinfunction "V18_P$19") (pintype "bidirectional"))
      (node (ref "U8") (pin "P$3") (pinfunction "V18_P$3") (pintype "bidirectional"))
      (node (ref "U9") (pin "2") (pinfunction "G_2") (pintype "bidirectional"))
    )
    (net (code "2") (name "3.3V") (class "Default")
      (node (ref "3V3") (pin "TP") (pinfunction "TP_TP") (pintype "input"))
      (node (ref "C1") (pin "P$1") (pinfunction "1_P$1") (pintype "passive"))
      (node (ref "C12") (pin "P$1") (pinfunction "1_P$1") (pintype "passive"))
      (node (ref "C14") (pin "P$1") (pinfunction "1_P$1") (pintype "passive"))
      (node (ref "C15") (pin "P$1") (pinfunction "1_P$1") (pintype "passive"))
      (node (ref "C16") (pin "P$1") (pinfunction "1_P$1") (pintype "passive"))
      (node (ref "C17") (pin "P$1") (pinfunction "1_P$1") (pintype "passive"))
      (node (ref "C26") (pin "P$1") (pinfunction "1_P$1") (pintype "passive"))
      (node (ref "C27") (pin "P$1") (pinfunction "1_P$1") (pintype "passive"))
      (node (ref "C28") (pin "P$1") (pinfunction "1_P$1") (pintype "passive"))
      (node (ref "C32") (pin "P$1") (pinfunction "1_P$1") (pintype "passive"))
      (node (ref "C34") (pin "P$1") (pinfunction "1_P$1") (pintype "passive"))
      (node (ref "C45") (pin "P$1") (pinfunction "1_P$1") (pintype "passive"))
      (node (ref "C46") (pin "P$1") (pinfunction "1_P$1") (pintype "passive"))
      (node (ref "C48") (pin "P$1") (pinfunction "1_P$1") (pintype "passive"))
      (node (ref "C5") (pin "P$1") (pinfunction "1_P$1") (pintype "passive"))
      (node (ref "C8") (pin "P$1") (pinfunction "1_P$1") (pintype "passive"))
      (node (ref "JLINK") (pin "5") (pinfunction "5_5") (pintype "passive"))
      (node (ref "L12") (pin "P$2") (pinfunction "2_P$2") (pintype "passive"))
      (node (ref "R1") (pin "2") (pinfunction "2_2") (pintype "passive"))
      (node (ref "R16") (pin "2") (pinfunction "2_2") (pintype "passive"))
      (node (ref "R22") (pin "2") (pinfunction "2_2") (pintype "passive"))
      (node (ref "R6") (pin "1") (pinfunction "1_1") (pintype "passive"))
      (node (ref "U11") (pin "6") (pinfunction "VDD_1_6") (pintype "power_in"))
      (node (ref "U11") (pin "8") (pinfunction "VDD_2_8") (pintype "power_in"))
      (node (ref "U12") (pin "6") (pinfunction "VDD_1_6") (pintype "power_in"))
      (node (ref "U12") (pin "8") (pinfunction "VDD_2_8") (pintype "power_in"))
      (node (ref "U13") (pin "1") (pinfunction "VDD_1") (pintype "bidirectional"))
      (node (ref "U13") (pin "17") (pinfunction "VDD_17") (pintype "bidirectional"))
      (node (ref "U13") (pin "5") (pinfunction "VDDA_5") (pintype "bidirectional"))
      (node (ref "U15") (pin "P$9") (pinfunction "VCC_P$9") (pintype "bidirectional"))
      (node (ref "U5") (pin "1") (pinfunction "IN_1") (pintype "input"))
      (node (ref "U5") (pin "3") (pinfunction "EN_3") (pintype "input"))
      (node (ref "U6") (pin "4") (pinfunction "VCC_4") (pintype "bidirectional"))
    )
    (net (code "3") (name "BOOT0") (class "Default")
      (node (ref "C38") (pin "P$1") (pinfunction "1_P$1") (pintype "passive"))
      (node (ref "R23") (pin "1") (pinfunction "1_1") (pintype "passive"))
      (node (ref "R3") (pin "1") (pinfunction "1_1") (pintype "passive"))
      (node (ref "U13") (pin "31") (pinfunction "BOOT0_31") (pintype "bidirectional"))
    )
    (net (code "4") (name "BOOT_CTRL") (class "Default")
      (node (ref "R3") (pin "2") (pinfunction "2_2") (pintype "passive"))
      (node (ref "U13") (pin "18") (pinfunction "PA8_18") (pintype "bidirectional"))
    )
    (net (code "5") (name "CS1") (class "Default")
      (node (ref "U11") (pin "15") (pinfunction "NSEL_15") (pintype "input"))
      (node (ref "U13") (pin "10") (pinfunction "PA4_10") (pintype "bidirectional"))
    )
    (net (code "6") (name "CS2") (class "Default")
      (node (ref "U12") (pin "15") (pinfunction "NSEL_15") (pintype "input"))
      (node (ref "U13") (pin "6") (pinfunction "PA0_6") (pintype "bidirectional"))
    )
    (net (code "7") (name "GND") (class "Default")
      (node (ref "C1") (pin "P$2") (pinfunction "2_P$2") (pintype "passive"))
      (node (ref "C11") (pin "P$2") (pinfunction "2_P$2") (pintype "passive"))
      (node (ref "C12") (pin "P$2") (pinfunction "2_P$2") (pintype "passive"))
      (node (ref "C13") (pin "P$1") (pinfunction "1_P$1") (pintype "passive"))
      (node (ref "C14") (pin "P$2") (pinfunction "2_P$2") (pintype "passive"))
      (node (ref "C15") (pin "P$2") (pinfunction "2_P$2") (pintype "passive"))
      (node (ref "C16") (pin "P$2") (pinfunction "2_P$2") (pintype "passive"))
      (node (ref "C17") (pin "P$2") (pinfunction "2_P$2") (pintype "passive"))
      (node (ref "C19") (pin "P$1") (pinfunction "1_P$1") (pintype "passive"))
      (node (ref "C21") (pin "P$2") (pinfunction "2_P$2") (pintype "passive"))
      (node (ref "C23") (pin "P$2") (pinfunction "2_P$2") (pintype "passive"))
      (node (ref "C24") (pin "P$2") (pinfunction "2_P$2") (pintype "passive"))
      (node (ref "C25") (pin "P$2") (pinfunction "2_P$2") (pintype "passive"))
      (node (ref "C26") (pin "P$2") (pinfunction "2_P$2") (pintype "passive"))
      (node (ref "C27") (pin "P$2") (pinfunction "2_P$2") (pintype "passive"))
      (node (ref "C28") (pin "P$2") (pinfunction "2_P$2") (pintype "passive"))
      (node (ref "C3") (pin "P$2") (pinfunction "2_P$2") (pintype "passive"))
      (node (ref "C30") (pin "P$2") (pinfunction "2_P$2") (pintype "passive"))
      (node (ref "C31") (pin "P$1") (pinfunction "1_P$1") (pintype "passive"))
      (node (ref "C32") (pin "P$2") (pinfunction "2_P$2") (pintype "passive"))
      (node (ref "C33") (pin "P$1") (pinfunction "1_P$1") (pintype "passive"))
      (node (ref "C34") (pin "P$2") (pinfunction "2_P$2") (pintype "passive"))
      (node (ref "C36") (pin "P$2") (pinfunction "2_P$2") (pintype "passive"))
      (node (ref "C37") (pin "P$2") (pinfunction "2_P$2") (pintype "passive"))
      (node (ref "C38") (pin "P$2") (pinfunction "2_P$2") (pintype "passive"))
      (node (ref "C39") (pin "P$2") (pinfunction "2_P$2") (pintype "passive"))
      (node (ref "C4") (pin "2") (pinfunction "22_2") (pintype "passive"))
      (node (ref "C41") (pin "P$2") (pinfunction "2_P$2") (pintype "passive"))
      (node (ref "C42") (pin "P$2") (pinfunction "2_P$2") (pintype "passive"))
      (node (ref "C43") (pin "P$2") (pinfunction "2_P$2") (pintype "passive"))
      (node (ref "C45") (pin "P$2") (pinfunction "2_P$2") (pintype "passive"))
      (node (ref "C46") (pin "P$2") (pinfunction "2_P$2") (pintype "passive"))
      (node (ref "C47") (pin "P$2") (pinfunction "2_P$2") (pintype "passive"))
      (node (ref "C48") (pin "P$2") (pinfunction "2_P$2") (pintype "passive"))
      (node (ref "C49") (pin "P$2") (pinfunction "2_P$2") (pintype "passive"))
      (node (ref "C5") (pin "P$2") (pinfunction "2_P$2") (pintype "passive"))
      (node (ref "C52") (pin "P$2") (pinfunction "2_P$2") (pintype "passive"))
      (node (ref "C53") (pin "P$2") (pinfunction "2_P$2") (pintype "passive"))
      (node (ref "C6") (pin "P$2") (pinfunction "2_P$2") (pintype "passive"))
      (node (ref "C7") (pin "P$2") (pinfunction "2_P$2") (pintype "passive"))
      (node (ref "C8") (pin "P$2") (pinfunction "2_P$2") (pintype "passive"))
      (node (ref "C9") (pin "P$2") (pinfunction "2_P$2") (pintype "passive"))
      (node (ref "D1") (pin "A") (pinfunction "A_A") (pintype "passive"))
      (node (ref "GND1") (pin "TP") (pinfunction "TP_TP") (pintype "input"))
      (node (ref "GND2") (pin "TP") (pinfunction "TP_TP") (pintype "input"))
      (node (ref "J$1") (pin "GND@0") (pinfunction "GND_GND@0") (pintype "bidirectional"))
      (node (ref "J$1") (pin "GND@1") (pinfunction "GND_GND@1") (pintype "bidirectional"))
      (node (ref "J$1") (pin "GND@2") (pinfunction "GND_GND@2") (pintype "bidirectional"))
      (node (ref "J$1") (pin "GND@3") (pinfunction "GND_GND@3") (pintype "bidirectional"))
      (node (ref "JLINK") (pin "1") (pinfunction "1_1") (pintype "passive"))
      (node (ref "JP1") (pin "7") (pinfunction "7_7") (pintype "bidirectional"))
      (node (ref "JP1") (pin "8") (pinfunction "8_8") (pintype "bidirectional"))
      (node (ref "L16") (pin "P$1") (pinfunction "1_P$1") (pintype "passive"))
      (node (ref "L22") (pin "P$1") (pinfunction "1_P$1") (pintype "passive"))
      (node (ref "R10") (pin "1") (pinfunction "1_1") (pintype "passive"))
      (node (ref "R12") (pin "1") (pinfunction "1_1") (pintype "passive"))
      (node (ref "R2") (pin "1") (pinfunction "1_1") (pintype "passive"))
      (node (ref "R23") (pin "2") (pinfunction "2_2") (pintype "passive"))
      (node (ref "R4") (pin "1") (pinfunction "1_1") (pintype "passive"))
      (node (ref "R9") (pin "1") (pinfunction "1_1") (pintype "passive"))
      (node (ref "S1") (pin "P$2") (pinfunction "S2_P$2") (pintype "bidirectional"))
      (node (ref "TP2") (pin "TP") (pinfunction "TP_TP") (pintype "input"))
      (node (ref "TP3") (pin "TP") (pinfunction "TP_TP") (pintype "input"))
      (node (ref "TP4") (pin "TP") (pinfunction "TP_TP") (pintype "input"))
      (node (ref "TP5") (pin "TP") (pinfunction "TP_TP") (pintype "input"))
      (node (ref "TP6") (pin "TP") (pinfunction "TP_TP") (pintype "input"))
      (node (ref "TP7") (pin "TP") (pinfunction "TP_TP") (pintype "input"))
      (node (ref "TP8") (pin "TP") (pinfunction "TP_TP") (pintype "input"))
      (node (ref "TP9") (pin "TP") (pinfunction "TP_TP") (pintype "input"))
      (node (ref "U1") (pin "2") (pinfunction "GND_2") (pintype "bidirectional"))
      (node (ref "U11") (pin "EXP") (pinfunction "PAD_EXP") (pintype "bidirectional"))
      (node (ref "U12") (pin "EXP") (pinfunction "PAD_EXP") (pintype "bidirectional"))
      (node (ref "U13") (pin "16") (pinfunction "VSS_16") (pintype "bidirectional"))
      (node (ref "U13") (pin "32") (pinfunction "VSS_32") (pintype "bidirectional"))
      (node (ref "U13") (pin "EXP") (pinfunction "PAD_EXP") (pintype "bidirectional"))
      (node (ref "U15") (pin "P$1") (pinfunction "GND_P$1") (pintype "bidirectional"))
      (node (ref "U15") (pin "P$10") (pinfunction "GND_P$10") (pintype "bidirectional"))
      (node (ref "U15") (pin "P$12") (pinfunction "GND_P$12") (pintype "bidirectional"))
      (node (ref "U15") (pin "P$13") (pinfunction "GND_P$13") (pintype "bidirectional"))
      (node (ref "U15") (pin "P$3") (pinfunction "GND_P$3") (pintype "bidirectional"))
      (node (ref "U15") (pin "P$4") (pinfunction "GND_P$4") (pintype "bidirectional"))
      (node (ref "U15") (pin "P$6") (pinfunction "GND_P$6") (pintype "bidirectional"))
      (node (ref "U3") (pin "P$4") (pinfunction "GND_P$4") (pintype "bidirectional"))
      (node (ref "U3") (pin "P$7") (pinfunction "GND_P$7") (pintype "bidirectional"))
      (node (ref "U4") (pin "4") (pinfunction "S_4") (pintype "bidirectional"))
      (node (ref "U5") (pin "2") (pinfunction "GND_2") (pintype "input"))
      (node (ref "U6") (pin "2") (pinfunction "GND_2") (pintype "bidirectional"))
      (node (ref "U7") (pin "2") (pinfunction "S_2") (pintype "passive"))
      (node (ref "U7") (pin "2@1") (pinfunction "PAD_2@1") (pintype "bidirectional"))
      (node (ref "U8") (pin "P$10") (pinfunction "GND_P$10") (pintype "bidirectional"))
      (node (ref "U8") (pin "P$2") (pinfunction "GND_P$2") (pintype "bidirectional"))
      (node (ref "U8") (pin "P$20") (pinfunction "GND_P$20") (pintype "bidirectional"))
      (node (ref "U9") (pin "4") (pinfunction "S_4") (pintype "bidirectional"))
      (node (ref "X1") (pin "2") (pinfunction "G2_2") (pintype "power_in"))
      (node (ref "X1") (pin "4") (pinfunction "G1_4") (pintype "power_in"))
      (node (ref "X2") (pin "2") (pinfunction "G2_2") (pintype "power_in"))
      (node (ref "X2") (pin "4") (pinfunction "G1_4") (pintype "power_in"))
    )
    (net (code "8") (name "GNSS_1PPS") (class "Default")
      (node (ref "U8") (pin "P$11") (pinfunction "TM_P$11") (pintype "bidirectional"))
      (node (ref "U9") (pin "5") (pinfunction "G_5") (pintype "bidirectional"))
    )
    (net (code "9") (name "GNSS_EN") (class "Default")
      (node (ref "R9") (pin "2") (pinfunction "2_2") (pintype "passive"))
      (node (ref "U13") (pin "2") (pinfunction "OSC_IN/PC14_2") (pintype "bidirectional"))
      (node (ref "U4") (pin "2") (pinfunction "G_2") (pintype "bidirectional"))
    )
    (net (code "10") (name "GNSS_EN_1V8") (class "Default")
      (node (ref "R10") (pin "2") (pinfunction "2_2") (pintype "passive"))
      (node (ref "U4") (pin "1") (pinfunction "S_1") (pintype "bidirectional"))
      (node (ref "U8") (pin "P$6") (pinfunction "ON_OFF_P$6") (pintype "bidirectional"))
    )
    (net (code "11") (name "GNSS_UART_TX") (class "Default")
      (node (ref "R15") (pin "1") (pinfunction "1_1") (pintype "passive"))
      (node (ref "U8") (pin "P$15") (pinfunction "TX_P$15") (pintype "bidirectional"))
      (node (ref "U9") (pin "1") (pinfunction "S_1") (pintype "bidirectional"))
    )
    (net (code "12") (name "I2C_SCL") (class "Default")
      (node (ref "U13") (pin "29") (pinfunction "PB6_29") (pintype "bidirectional"))
      (node (ref "U6") (pin "1") (pinfunction "SCL_1") (pintype "bidirectional"))
    )
    (net (code "13") (name "I2C_SDA") (class "Default")
      (node (ref "U13") (pin "30") (pinfunction "PB7_30") (pintype "bidirectional"))
      (node (ref "U6") (pin "3") (pinfunction "SDA_3") (pintype "bidirectional"))
    )
    (net (code "14") (name "MCU_GNSS_1PPS") (class "Default")
      (node (ref "U13") (pin "8") (pinfunction "PA2_8") (pintype "bidirectional"))
      (node (ref "U9") (pin "3") (pinfunction "D_3") (pintype "bidirectional"))
    )
    (net (code "15") (name "MCU_GNSS_UART_RX") (class "Default")
      (node (ref "R16") (pin "1") (pinfunction "1_1") (pintype "passive"))
      (node (ref "U13") (pin "9") (pinfunction "PA3_9") (pintype "bidirectional"))
      (node (ref "U9") (pin "6") (pinfunction "D_6") (pintype "bidirectional"))
    )
    (net (code "16") (name "MCU_UART_RX") (class "Default")
      (node (ref "JP1") (pin "3") (pinfunction "3_3") (pintype "bidirectional"))
      (node (ref "RX") (pin "TP") (pinfunction "TP_TP") (pintype "input"))
      (node (ref "U13") (pin "20") (pinfunction "PA10_20") (pintype "bidirectional"))
    )
    (net (code "17") (name "MCU_UART_TX") (class "Default")
      (node (ref "JP1") (pin "6") (pinfunction "6_6") (pintype "bidirectional"))
      (node (ref "TX") (pin "TP") (pinfunction "TP_TP") (pintype "input"))
      (node (ref "U13") (pin "19") (pinfunction "PA9_19") (pintype "bidirectional"))
    )
    (net (code "18") (name "MISO") (class "Default")
      (node (ref "U11") (pin "13") (pinfunction "SDO_13") (pintype "output"))
      (node (ref "U12") (pin "13") (pinfunction "SDO_13") (pintype "output"))
      (node (ref "U13") (pin "12") (pinfunction "PA6_12") (pintype "bidirectional"))
    )
    (net (code "19") (name "MOSI") (class "Default")
      (node (ref "U11") (pin "14") (pinfunction "SDI_14") (pintype "input"))
      (node (ref "U12") (pin "14") (pinfunction "SDI_14") (pintype "input"))
      (node (ref "U13") (pin "13") (pinfunction "PA7_13") (pintype "bidirectional"))
    )
    (net (code "20") (name "NRST") (class "Default")
      (node (ref "JLINK") (pin "2") (pinfunction "2_2") (pintype "passive"))
      (node (ref "NRST") (pin "TP") (pinfunction "TP_TP") (pintype "input"))
      (node (ref "S1") (pin "P$1") (pinfunction "S1_P$1") (pintype "bidirectional"))
      (node (ref "U13") (pin "4") (pinfunction "NRST_4") (pintype "bidirectional"))
    )
    (net (code "21") (name "Net-(C2-1)") (class "Default")
      (node (ref "C2") (pin "P$1") (pinfunction "1_P$1") (pintype "passive"))
      (node (ref "U1") (pin "1") (pinfunction "BS_1") (pintype "bidirectional"))
    )
    (net (code "22") (name "Net-(C2-2)") (class "Default")
      (node (ref "C2") (pin "P$2") (pinfunction "2_P$2") (pintype "passive"))
      (node (ref "D1") (pin "C") (pinfunction "C_C") (pintype "passive"))
      (node (ref "L12") (pin "P$1") (pinfunction "1_P$1") (pintype "passive"))
      (node (ref "U1") (pin "6") (pinfunction "SW_6") (pintype "bidirectional"))
    )
    (net (code "23") (name "Net-(C4-11)") (class "Default")
      (node (ref "C4") (pin "1") (pinfunction "11_1") (pintype "passive"))
      (node (ref "C43") (pin "P$1") (pinfunction "1_P$1") (pintype "passive"))
      (node (ref "L2") (pin "P$1") (pinfunction "1_P$1") (pintype "passive"))
      (node (ref "U1") (pin "4") (pinfunction "EN_4") (pintype "bidirectional"))
      (node (ref "U1") (pin "5") (pinfunction "IN_5") (pintype "bidirectional"))
    )
    (net (code "24") (name "Net-(C10-1)") (class "Default")
      (node (ref "C10") (pin "P$1") (pinfunction "1_P$1") (pintype "passive"))
      (node (ref "C13") (pin "P$2") (pinfunction "2_P$2") (pintype "passive"))
      (node (ref "L14") (pin "P$1") (pinfunction "1_P$1") (pintype "passive"))
      (node (ref "L22") (pin "P$2") (pinfunction "2_P$2") (pintype "passive"))
    )
    (net (code "25") (name "Net-(C10-2)") (class "Default")
      (node (ref "C10") (pin "P$2") (pinfunction "2_P$2") (pintype "passive"))
      (node (ref "L21") (pin "P$2") (pinfunction "2_P$2") (pintype "passive"))
    )
    (net (code "26") (name "Net-(C11-1)") (class "Default")
      (node (ref "C11") (pin "P$1") (pinfunction "1_P$1") (pintype "passive"))
      (node (ref "L17") (pin "P$2") (pinfunction "2_P$2") (pintype "passive"))
      (node (ref "R11") (pin "1") (pinfunction "1_1") (pintype "passive"))
      (node (ref "R12") (pin "2") (pinfunction "2_2") (pintype "passive"))
    )
    (net (code "27") (name "Net-(C18-1)") (class "Default")
      (node (ref "C18") (pin "P$1") (pinfunction "1_P$1") (pintype "passive"))
      (node (ref "L8") (pin "P$1") (pinfunction "1_P$1") (pintype "passive"))
      (node (ref "U11") (pin "2") (pinfunction "RXP_2") (pintype "input"))
    )
    (net (code "28") (name "Net-(C19-2)") (class "Default")
      (node (ref "C19") (pin "P$2") (pinfunction "2_P$2") (pintype "passive"))
      (node (ref "L8") (pin "P$2") (pinfunction "2_P$2") (pintype "passive"))
      (node (ref "U11") (pin "3") (pinfunction "RXN_3") (pintype "input"))
    )
    (net (code "29") (name "Net-(C20-1)") (class "Default")
      (node (ref "C20") (pin "P$1") (pinfunction "1_P$1") (pintype "passive"))
      (node (ref "L13") (pin "P$1") (pinfunction "1_P$1") (pintype "passive"))
      (node (ref "U12") (pin "2") (pinfunction "RXP_2") (pintype "input"))
    )
    (net (code "30") (name "Net-(C21-1)") (class "Default")
      (node (ref "C21") (pin "P$1") (pinfunction "1_P$1") (pintype "passive"))
      (node (ref "L5") (pin "P$1") (pinfunction "1_P$1") (pintype "passive"))
      (node (ref "R22") (pin "1") (pinfunction "1_1") (pintype "passive"))
    )
    (net (code "31") (name "Net-(C22-1)") (class "Default")
      (node (ref "C22") (pin "P$1") (pinfunction "1_P$1") (pintype "passive"))
      (node (ref "L5") (pin "P$2") (pinfunction "2_P$2") (pintype "passive"))
      (node (ref "U11") (pin "4") (pinfunction "TX_4") (pintype "output"))
    )
    (net (code "32") (name "Net-(C22-2)") (class "Default")
      (node (ref "C22") (pin "P$2") (pinfunction "2_P$2") (pintype "passive"))
      (node (ref "L1") (pin "P$1") (pinfunction "1_P$1") (pintype "passive"))
    )
    (net (code "33") (name "Net-(C23-1)") (class "Default")
      (node (ref "C23") (pin "P$1") (pinfunction "1_P$1") (pintype "passive"))
      (node (ref "L1") (pin "P$2") (pinfunction "2_P$2") (pintype "passive"))
      (node (ref "L6") (pin "P$1") (pinfunction "1_P$1") (pintype "passive"))
    )
    (net (code "34") (name "Net-(C24-1)") (class "Default")
      (node (ref "C24") (pin "P$1") (pinfunction "1_P$1") (pintype "passive"))
      (node (ref "L6") (pin "P$2") (pinfunction "2_P$2") (pintype "passive"))
      (node (ref "L7") (pin "P$1") (pinfunction "1_P$1") (pintype "passive"))
    )
    (net (code "35") (name "Net-(C25-1)") (class "Default")
      (node (ref "C25") (pin "P$1") (pinfunction "1_P$1") (pintype "passive"))
      (node (ref "L11") (pin "P$1") (pinfunction "1_P$1") (pintype "passive"))
      (node (ref "L7") (pin "P$2") (pinfunction "2_P$2") (pintype "passive"))
    )
    (net (code "36") (name "Net-(C29-2)") (class "Default")
      (node (ref "C29") (pin "P$2") (pinfunction "2_P$2") (pintype "passive"))
      (node (ref "C30") (pin "P$1") (pinfunction "1_P$1") (pintype "passive"))
      (node (ref "L3") (pin "P$1") (pinfunction "1_P$1") (pintype "passive"))
    )
    (net (code "37") (name "Net-(C31-2)") (class "Default")
      (node (ref "C31") (pin "P$2") (pinfunction "2_P$2") (pintype "passive"))
      (node (ref "L13") (pin "P$2") (pinfunction "2_P$2") (pintype "passive"))
      (node (ref "U12") (pin "3") (pinfunction "RXN_3") (pintype "input"))
    )
    (net (code "38") (name "Net-(C33-2)") (class "Default")
      (node (ref "C33") (pin "P$2") (pinfunction "2_P$2") (pintype "passive"))
      (node (ref "C35") (pin "P$1") (pinfunction "1_P$1") (pintype "passive"))
      (node (ref "C40") (pin "P$2") (pinfunction "2_P$2") (pintype "passive"))
      (node (ref "L16") (pin "P$2") (pinfunction "2_P$2") (pintype "passive"))
    )
    (net (code "39") (name "Net-(C35-2)") (class "Default")
      (node (ref "C35") (pin "P$2") (pinfunction "2_P$2") (pintype "passive"))
      (node (ref "L14") (pin "P$2") (pinfunction "2_P$2") (pintype "passive"))
    )
    (net (code "40") (name "Net-(C36-1)") (class "Default")
      (node (ref "C36") (pin "P$1") (pinfunction "1_P$1") (pintype "passive"))
      (node (ref "L10") (pin "P$1") (pinfunction "1_P$1") (pintype "passive"))
      (node (ref "L9") (pin "P$2") (pinfunction "2_P$2") (pintype "passive"))
    )
    (net (code "41") (name "Net-(C37-1)") (class "Default")
      (node (ref "C37") (pin "P$1") (pinfunction "1_P$1") (pintype "passive"))
      (node (ref "C39") (pin "P$1") (pinfunction "1_P$1") (pintype "passive"))
      (node (ref "L4") (pin "P$2") (pinfunction "2_P$2") (pintype "passive"))
      (node (ref "L9") (pin "P$1") (pinfunction "1_P$1") (pintype "passive"))
      (node (ref "U7") (pin "3") (pinfunction "D_3") (pintype "passive"))
    )
    (net (code "42") (name "Net-(C40-1)") (class "Default")
      (node (ref "C40") (pin "P$1") (pinfunction "1_P$1") (pintype "passive"))
      (node (ref "L15") (pin "P$1") (pinfunction "1_P$1") (pintype "passive"))
    )
    (net (code "43") (name "Net-(C42-1)") (class "Default")
      (node (ref "C42") (pin "P$1") (pinfunction "1_P$1") (pintype "passive"))
      (node (ref "C52") (pin "P$1") (pinfunction "1_P$1") (pintype "passive"))
      (node (ref "L10") (pin "P$2") (pinfunction "2_P$2") (pintype "passive"))
      (node (ref "L23") (pin "P$1") (pinfunction "1_P$1") (pintype "passive"))
    )
    (net (code "44") (name "Net-(C44-1)") (class "Default")
      (node (ref "C44") (pin "P$1") (pinfunction "1_P$1") (pintype "passive"))
      (node (ref "C53") (pin "P$1") (pinfunction "1_P$1") (pintype "passive"))
      (node (ref "L23") (pin "P$2") (pinfunction "2_P$2") (pintype "passive"))
    )
    (net (code "45") (name "Net-(D2-PadA)") (class "Default")
      (node (ref "D2") (pin "A") (pinfunction "A_A") (pintype "passive"))
      (node (ref "JP1") (pin "1") (pinfunction "1_1") (pintype "bidirectional"))
      (node (ref "JP1") (pin "2") (pinfunction "2_2") (pintype "bidirectional"))
      (node (ref "V_IN") (pin "TP") (pinfunction "TP_TP") (pintype "input"))
    )
    (net (code "46") (name "Net-(D2-PadC)") (class "Default")
      (node (ref "D2") (pin "C") (pinfunction "C_C") (pintype "passive"))
      (node (ref "F1") (pin "1") (pinfunction "1_1") (pintype "passive"))
    )
    (net (code "47") (name "Net-(J$1-SIGNAL)") (class "Default")
      (node (ref "J$1") (pin "SIG") (pinfunction "SIGNAL_SIG") (pintype "bidirectional"))
      (node (ref "TP1") (pin "TP") (pinfunction "TP_TP") (pintype "input"))
      (node (ref "U15") (pin "P$2") (pinfunction "RF1_P$2") (pintype "bidirectional"))
    )
    (net (code "48") (name "Net-(L17-1)") (class "Default")
      (node (ref "L17") (pin "P$1") (pinfunction "1_P$1") (pintype "passive"))
      (node (ref "L3") (pin "P$2") (pinfunction "2_P$2") (pintype "passive"))
      (node (ref "U7") (pin "1") (pinfunction "G_1") (pintype "passive"))
    )
    (net (code "49") (name "Net-(U1-FB)") (class "Default")
      (node (ref "R1") (pin "1") (pinfunction "1_1") (pintype "passive"))
      (node (ref "R2") (pin "2") (pinfunction "2_2") (pintype "passive"))
      (node (ref "U1") (pin "3") (pinfunction "FB_3") (pintype "bidirectional"))
    )
    (net (code "50") (name "Net-(U3-ADJ)") (class "Default")
      (node (ref "R4") (pin "2") (pinfunction "2_2") (pintype "passive"))
      (node (ref "R5") (pin "1") (pinfunction "1_1") (pintype "passive"))
      (node (ref "U3") (pin "P$2") (pinfunction "ADJ_P$2") (pintype "bidirectional"))
    )
    (net (code "51") (name "Net-(U8-GPIO6)") (class "Default")
      (node (ref "R14") (pin "1") (pinfunction "1_1") (pintype "passive"))
      (node (ref "U8") (pin "P$13") (pinfunction "GPIO6_P$13") (pintype "bidirectional"))
    )
    (net (code "52") (name "Net-(U10-RF)") (class "Default")
      (node (ref "U10") (pin "P$1") (pinfunction "RF_P$1") (pintype "bidirectional"))
      (node (ref "U8") (pin "P$1") (pinfunction "RF_IN_P$1") (pintype "bidirectional"))
    )
    (net (code "53") (name "Net-(U11-XIN)") (class "Default")
      (node (ref "U11") (pin "17") (pinfunction "XIN_17") (pintype "input"))
      (node (ref "X1") (pin "3") (pinfunction "X2_3") (pintype "bidirectional"))
    )
    (net (code "54") (name "Net-(U11-XOUT)") (class "Default")
      (node (ref "U11") (pin "16") (pinfunction "XOUT_16") (pintype "bidirectional"))
      (node (ref "X1") (pin "1") (pinfunction "X1_1") (pintype "bidirectional"))
    )
    (net (code "55") (name "Net-(U12-XIN)") (class "Default")
      (node (ref "U12") (pin "17") (pinfunction "XIN_17") (pintype "input"))
      (node (ref "X2") (pin "3") (pinfunction "X2_3") (pintype "bidirectional"))
    )
    (net (code "56") (name "Net-(U12-XOUT)") (class "Default")
      (node (ref "U12") (pin "16") (pinfunction "XOUT_16") (pintype "bidirectional"))
      (node (ref "X2") (pin "1") (pinfunction "X1_1") (pintype "bidirectional"))
    )
    (net (code "57") (name "PA_IN") (class "Default")
      (node (ref "C29") (pin "P$1") (pinfunction "1_P$1") (pintype "passive"))
      (node (ref "L11") (pin "P$2") (pinfunction "2_P$2") (pintype "passive"))
    )
    (net (code "58") (name "PA_OUT") (class "Default")
      (node (ref "C44") (pin "P$2") (pinfunction "2_P$2") (pintype "passive"))
      (node (ref "U15") (pin "P$5") (pinfunction "RF3_P$5") (pintype "bidirectional"))
    )
    (net (code "59") (name "RF_IN") (class "Default")
      (node (ref "L21") (pin "P$1") (pinfunction "1_P$1") (pintype "passive"))
      (node (ref "U15") (pin "P$11") (pinfunction "RF2_P$11") (pintype "bidirectional"))
    )
    (net (code "60") (name "RX_EN") (class "Default")
      (node (ref "R19") (pin "1") (pinfunction "1_1") (pintype "passive"))
      (node (ref "U15") (pin "P$7") (pinfunction "CTRL_P$7") (pintype "bidirectional"))
      (node (ref "U4") (pin "3") (pinfunction "D_3") (pintype "bidirectional"))
    )
    (net (code "61") (name "RX_IC_CLK") (class "Default")
      (node (ref "U12") (pin "20") (pinfunction "GPIO3_20") (pintype "bidirectional"))
      (node (ref "U13") (pin "26") (pinfunction "PB3_26") (pintype "bidirectional"))
    )
    (net (code "62") (name "RX_IC_DATA") (class "Default")
      (node (ref "U12") (pin "10") (pinfunction "GPIO1_10") (pintype "bidirectional"))
      (node (ref "U13") (pin "27") (pinfunction "PB4_27") (pintype "bidirectional"))
    )
    (net (code "63") (name "RX_IN") (class "Default")
      (node (ref "C18") (pin "P$2") (pinfunction "2_P$2") (pintype "passive"))
      (node (ref "C20") (pin "P$2") (pinfunction "2_P$2") (pintype "passive"))
      (node (ref "L15") (pin "P$2") (pinfunction "2_P$2") (pintype "passive"))
    )
    (net (code "64") (name "SCK") (class "Default")
      (node (ref "U11") (pin "12") (pinfunction "SCLK_12") (pintype "input"))
      (node (ref "U12") (pin "12") (pinfunction "SCLK_12") (pintype "input"))
      (node (ref "U13") (pin "11") (pinfunction "PA5_11") (pintype "bidirectional"))
    )
    (net (code "65") (name "SDN1") (class "Default")
      (node (ref "U11") (pin "1") (pinfunction "SDN_1") (pintype "input"))
      (node (ref "U13") (pin "14") (pinfunction "PB0_14") (pintype "bidirectional"))
    )
    (net (code "66") (name "SDN2") (class "Default")
      (node (ref "U12") (pin "1") (pinfunction "SDN_1") (pintype "input"))
      (node (ref "U13") (pin "25") (pinfunction "PA15_25") (pintype "bidirectional"))
    )
    (net (code "67") (name "SPARE") (class "Default")
      (node (ref "JP1") (pin "5") (pinfunction "5_5") (pintype "bidirectional"))
      (node (ref "U13") (pin "21") (pinfunction "PA11_21") (pintype "bidirectional"))
    )
    (net (code "68") (name "SWCLK") (class "Default")
      (node (ref "JLINK") (pin "3") (pinfunction "3_3") (pintype "passive"))
      (node (ref "SWCLK") (pin "TP") (pinfunction "TP_TP") (pintype "input"))
      (node (ref "U13") (pin "24") (pinfunction "PA14_24") (pintype "bidirectional"))
    )
    (net (code "69") (name "SWDIO") (class "Default")
      (node (ref "JLINK") (pin "4") (pinfunction "4_4") (pintype "passive"))
      (node (ref "SWDIO") (pin "TP") (pinfunction "TP_TP") (pintype "input"))
      (node (ref "U13") (pin "23") (pinfunction "PA13_23") (pintype "bidirectional"))
    )
    (net (code "70") (name "TRX_IC_CLOCK") (class "Default")
      (node (ref "U11") (pin "19") (pinfunction "GPIO2_19") (pintype "bidirectional"))
      (node (ref "U13") (pin "7") (pinfunction "PA1_7") (pintype "bidirectional"))
    )
    (net (code "71") (name "TRX_IC_DATA") (class "Default")
      (node (ref "U11") (pin "10") (pinfunction "GPIO1_10") (pintype "bidirectional"))
      (node (ref "U13") (pin "15") (pinfunction "PB1_15") (pintype "bidirectional"))
    )
    (net (code "72") (name "TX_CTRL") (class "Default")
      (node (ref "R11") (pin "2") (pinfunction "2_2") (pintype "passive"))
      (node (ref "U13") (pin "28") (pinfunction "PB5_28") (pintype "bidirectional"))
      (node (ref "U4") (pin "5") (pinfunction "G_5") (pintype "bidirectional"))
    )
    (net (code "73") (name "TX_DISABLE") (class "Default")
      (node (ref "JP1") (pin "4") (pinfunction "4_4") (pintype "bidirectional"))
      (node (ref "TX_OFF") (pin "TP") (pinfunction "TP_TP") (pintype "input"))
      (node (ref "U13") (pin "22") (pinfunction "PA12_22") (pintype "bidirectional"))
    )
    (net (code "74") (name "V_BAT") (class "Default")
      (node (ref "C3") (pin "P$1") (pinfunction "1_P$1") (pintype "passive"))
      (node (ref "C41") (pin "P$1") (pinfunction "1_P$1") (pintype "passive"))
      (node (ref "C47") (pin "P$1") (pinfunction "1_P$1") (pintype "passive"))
      (node (ref "C6") (pin "P$1") (pinfunction "1_P$1") (pintype "passive"))
      (node (ref "F1") (pin "2") (pinfunction "2_2") (pintype "passive"))
      (node (ref "L2") (pin "P$2") (pinfunction "2_P$2") (pintype "passive"))
      (node (ref "U3") (pin "P$5") (pinfunction "EN_P$5") (pintype "bidirectional"))
      (node (ref "U3") (pin "P$6") (pinfunction "VIN_P$6") (pintype "bidirectional"))
    )
    (net (code "75") (name "V_PA") (class "Default")
      (node (ref "C49") (pin "P$1") (pinfunction "1_P$1") (pintype "passive"))
      (node (ref "C7") (pin "P$1") (pinfunction "1_P$1") (pintype "passive"))
      (node (ref "L4") (pin "P$1") (pinfunction "1_P$1") (pintype "passive"))
      (node (ref "R5") (pin "2") (pinfunction "2_2") (pintype "passive"))
      (node (ref "U3") (pin "P$1") (pinfunction "VOUT_P$1") (pintype "bidirectional"))
      (node (ref "V_PA") (pin "TP") (pinfunction "TP_TP") (pintype "input"))
    )
    (net (code "76") (name "unconnected-(S1-S1-PadP$4)") (class "Default")
      (node (ref "S1") (pin "P$4") (pinfunction "S1_P$4") (pintype "bidirectional"))
    )
    (net (code "77") (name "unconnected-(S1-S2-PadP$3)") (class "Default")
      (node (ref "S1") (pin "P$3") (pinfunction "S2_P$3") (pintype "bidirectional"))
    )
    (net (code "78") (name "unconnected-(U3-PG-PadP$3)") (class "Default")
      (node (ref "U3") (pin "P$3") (pinfunction "PG_P$3") (pintype "bidirectional"))
    )
    (net (code "79") (name "unconnected-(U5-BP-Pad4)") (class "Default")
      (node (ref "U5") (pin "4") (pinfunction "BP_4") (pintype "input"))
    )
    (net (code "80") (name "unconnected-(U8-BOOTSEL-PadP$9)") (class "Default")
      (node (ref "U8") (pin "P$9") (pinfunction "BOOTSEL_P$9") (pintype "bidirectional"))
    )
    (net (code "81") (name "unconnected-(U8-GPIO0-PadP$18)") (class "Default")
      (node (ref "U8") (pin "P$18") (pinfunction "GPIO0_P$18") (pintype "bidirectional"))
    )
    (net (code "82") (name "unconnected-(U8-GPIO1-PadP$17)") (class "Default")
      (node (ref "U8") (pin "P$17") (pinfunction "GPIO1_P$17") (pintype "bidirectional"))
    )
    (net (code "83") (name "unconnected-(U8-GPIO7-PadP$12)") (class "Default")
      (node (ref "U8") (pin "P$12") (pinfunction "GPIO7_P$12") (pintype "bidirectional"))
    )
    (net (code "84") (name "unconnected-(U8-GPIO8-PadP$5)") (class "Default")
      (node (ref "U8") (pin "P$5") (pinfunction "GPIO8_P$5") (pintype "bidirectional"))
    )
    (net (code "85") (name "unconnected-(U8-NC-PadP$4)") (class "Default")
      (node (ref "U8") (pin "P$4") (pinfunction "NC_P$4") (pintype "bidirectional"))
    )
    (net (code "86") (name "unconnected-(U8-NC-PadP$16)") (class "Default")
      (node (ref "U8") (pin "P$16") (pinfunction "NC_P$16") (pintype "bidirectional"))
    )
    (net (code "87") (name "unconnected-(U8-NRESET-PadP$8)") (class "Default")
      (node (ref "U8") (pin "P$8") (pinfunction "NRESET_P$8") (pintype "bidirectional"))
    )
    (net (code "88") (name "unconnected-(U8-RX-PadP$14)") (class "Default")
      (node (ref "U8") (pin "P$14") (pinfunction "RX_P$14") (pintype "bidirectional"))
    )
    (net (code "89") (name "unconnected-(U8-SYS_ON-PadP$7)") (class "Default")
      (node (ref "U8") (pin "P$7") (pinfunction "SYS_ON_P$7") (pintype "bidirectional"))
    )
    (net (code "90") (name "unconnected-(U10-PAD-PadP$2)") (class "Default")
      (node (ref "U10") (pin "P$2") (pinfunction "PAD_P$2") (pintype "bidirectional"))
    )
    (net (code "91") (name "unconnected-(U11-GNDX-Pad18)") (class "Default")
      (node (ref "U11") (pin "18") (pinfunction "GNDX_18") (pintype "bidirectional"))
    )
    (net (code "92") (name "unconnected-(U11-GPIO0-Pad9)") (class "Default")
      (node (ref "U11") (pin "9") (pinfunction "GPIO0_9") (pintype "bidirectional"))
    )
    (net (code "93") (name "unconnected-(U11-GPIO3-Pad20)") (class "Default")
      (node (ref "U11") (pin "20") (pinfunction "GPIO3_20") (pintype "bidirectional"))
    )
    (net (code "94") (name "unconnected-(U11-NIRQ-Pad11)") (class "Default")
      (node (ref "U11") (pin "11") (pinfunction "NIRQ_11") (pintype "bidirectional"))
    )
    (net (code "95") (name "unconnected-(U11-TXRAMP-Pad7)") (class "Default")
      (node (ref "U11") (pin "7") (pinfunction "TXRAMP_7") (pintype "bidirectional"))
    )
    (net (code "96") (name "unconnected-(U12-GNDX-Pad18)") (class "Default")
      (node (ref "U12") (pin "18") (pinfunction "GNDX_18") (pintype "bidirectional"))
    )
    (net (code "97") (name "unconnected-(U12-GPIO0-Pad9)") (class "Default")
      (node (ref "U12") (pin "9") (pinfunction "GPIO0_9") (pintype "bidirectional"))
    )
    (net (code "98") (name "unconnected-(U12-GPIO2-Pad19)") (class "Default")
      (node (ref "U12") (pin "19") (pinfunction "GPIO2_19") (pintype "bidirectional"))
    )
    (net (code "99") (name "unconnected-(U12-NIRQ-Pad11)") (class "Default")
      (node (ref "U12") (pin "11") (pinfunction "NIRQ_11") (pintype "bidirectional"))
    )
    (net (code "100") (name "unconnected-(U12-TX-Pad4)") (class "Default")
      (node (ref "U12") (pin "4") (pinfunction "TX_4") (pintype "output"))
    )
    (net (code "101") (name "unconnected-(U12-TXRAMP-Pad7)") (class "Default")
      (node (ref "U12") (pin "7") (pinfunction "TXRAMP_7") (pintype "bidirectional"))
    )
    (net (code "102") (name "~{EEPROM_WRITE_EN}") (class "Default")
      (node (ref "R6") (pin "2") (pinfunction "2_2") (pintype "passive"))
      (node (ref "U13") (pin "3") (pinfunction "OSC_OUT/PC15_3") (pintype "bidirectional"))
      (node (ref "U6") (pin "5") (pinfunction "WP_5") (pintype "bidirectional"))
    )
  )
)
